# Circuit.net
KiCad netlist of a schematic drawn in EAGLE
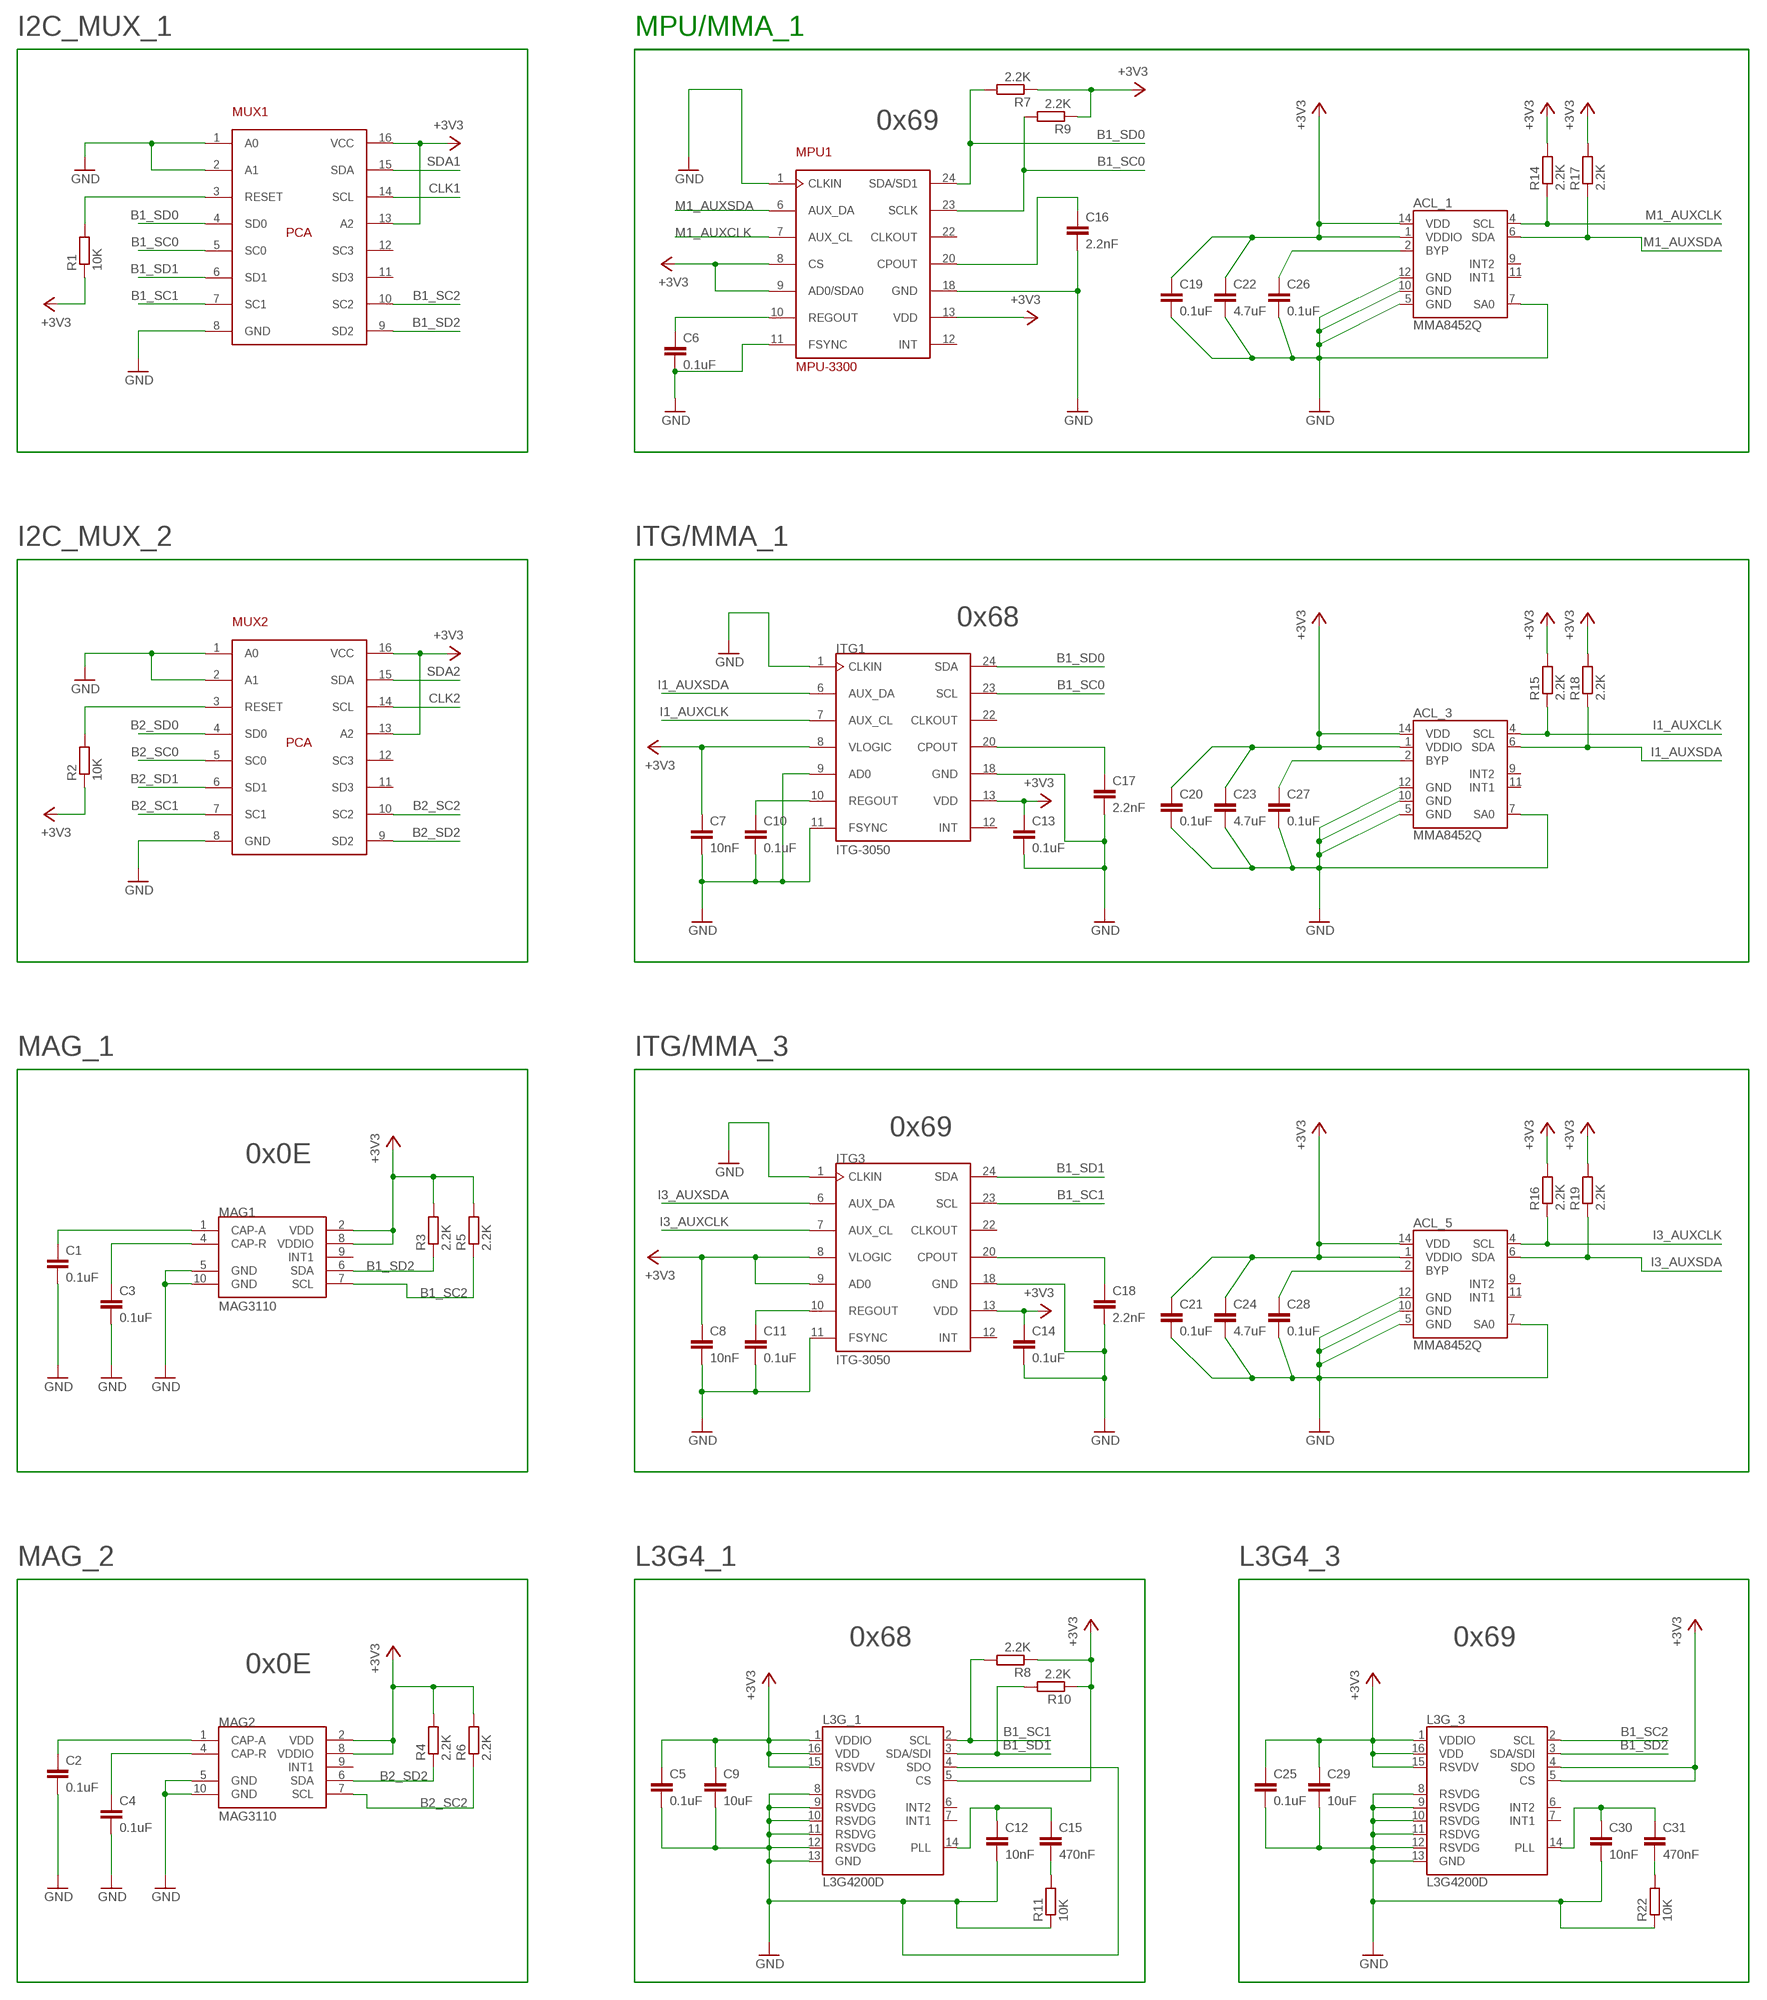
[diagram p0: schematic, sheet 1, part 1 of 2]
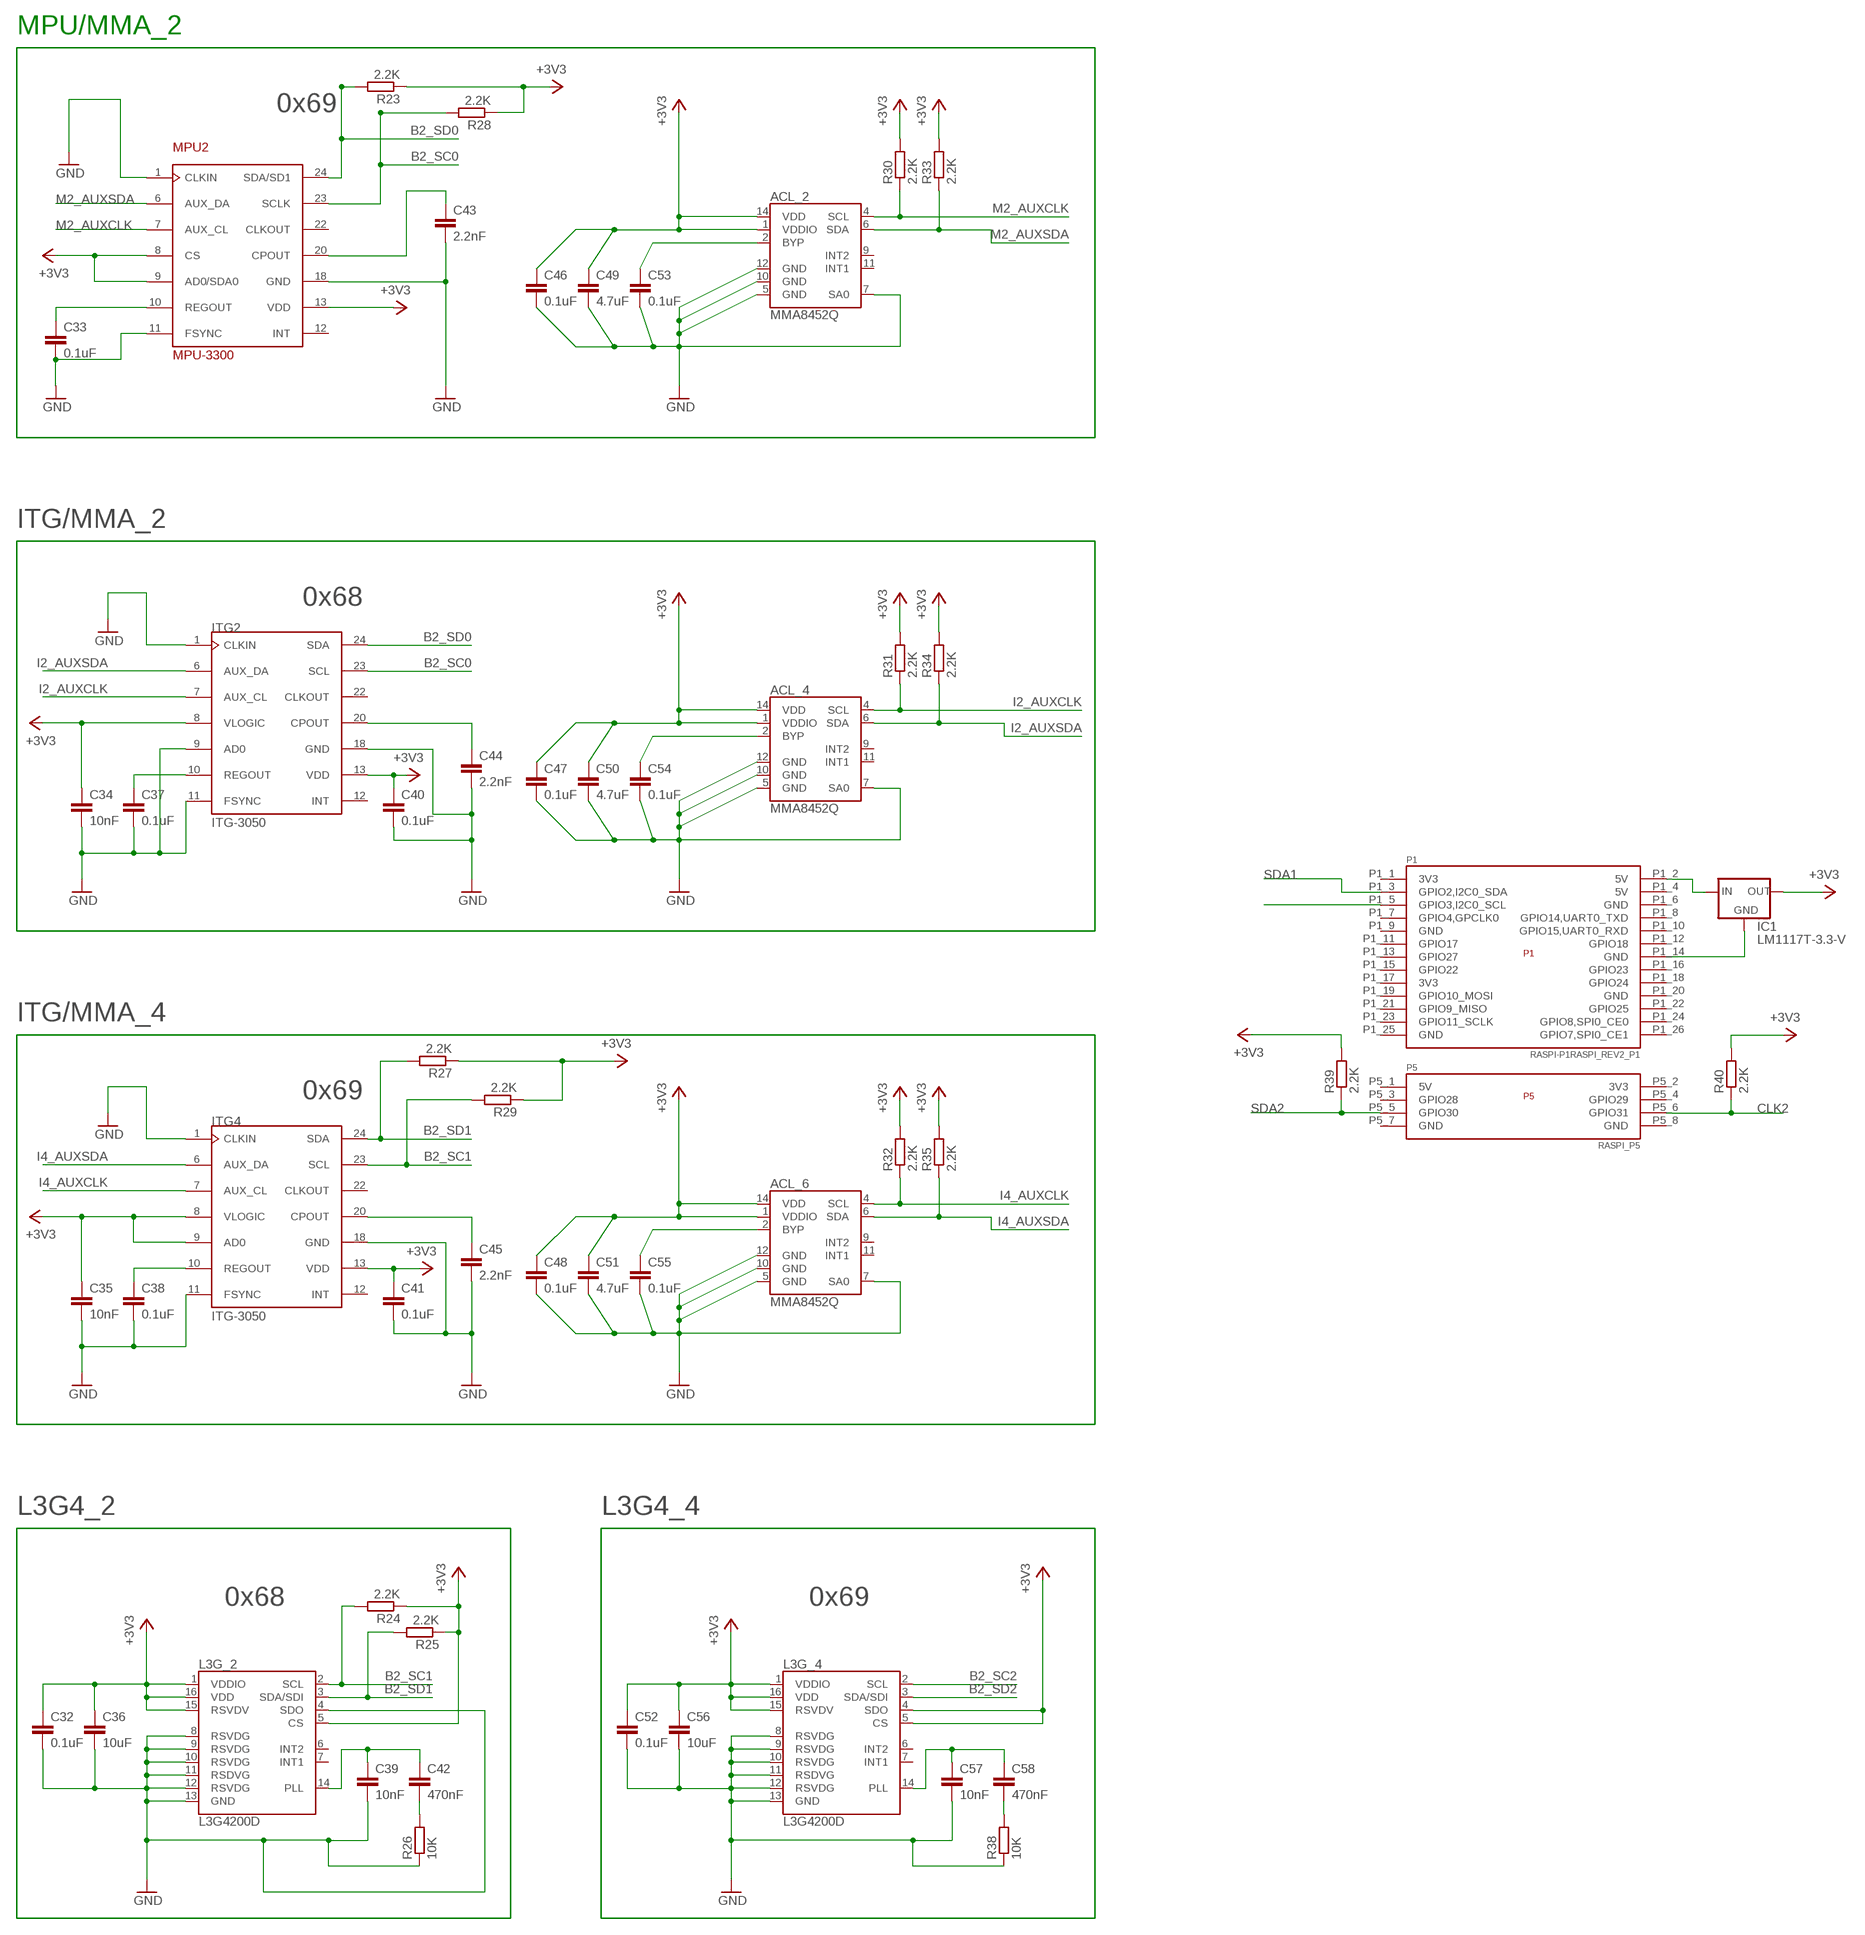
[diagram p1: schematic, sheet 1, part 2 of 2]

(export (version "E")
  (design (tool "Eeschema 10.0.6"))
  (components
    (comp (ref "ACL_1")
      (value "MMA8452Q")
      (footprint "eagle-import:QFN-16_0.5MM")
      (libsource (lib "eagle-import") (part "MMA8452Q"))
    )
    (comp (ref "ACL_2")
      (value "MMA8452Q")
      (footprint "eagle-import:QFN-16_0.5MM")
      (libsource (lib "eagle-import") (part "MMA8452Q"))
    )
    (comp (ref "ACL_3")
      (value "MMA8452Q")
      (footprint "eagle-import:QFN-16_0.5MM")
      (libsource (lib "eagle-import") (part "MMA8452Q"))
    )
    (comp (ref "ACL_4")
      (value "MMA8452Q")
      (footprint "eagle-import:QFN-16_0.5MM")
      (libsource (lib "eagle-import") (part "MMA8452Q"))
    )
    (comp (ref "ACL_5")
      (value "MMA8452Q")
      (footprint "eagle-import:QFN-16_0.5MM")
      (libsource (lib "eagle-import") (part "MMA8452Q"))
    )
    (comp (ref "ACL_6")
      (value "MMA8452Q")
      (footprint "eagle-import:QFN-16_0.5MM")
      (libsource (lib "eagle-import") (part "MMA8452Q"))
    )
    (comp (ref "C1")
      (value "0.1uF")
      (footprint "eagle-import:0603-CAP")
      (libsource (lib "eagle-import") (part "CAP0603-CAP"))
    )
    (comp (ref "C2")
      (value "0.1uF")
      (footprint "eagle-import:0603-CAP")
      (libsource (lib "eagle-import") (part "CAP0603-CAP"))
    )
    (comp (ref "C3")
      (value "0.1uF")
      (footprint "eagle-import:0603-CAP")
      (libsource (lib "eagle-import") (part "CAP0603-CAP"))
    )
    (comp (ref "C4")
      (value "0.1uF")
      (footprint "eagle-import:0603-CAP")
      (libsource (lib "eagle-import") (part "CAP0603-CAP"))
    )
    (comp (ref "C5")
      (value "0.1uF")
      (footprint "eagle-import:0603-CAP")
      (libsource (lib "eagle-import") (part "CAP0603-CAP"))
    )
    (comp (ref "C6")
      (value "0.1uF")
      (footprint "eagle-import:0603-CAP")
      (libsource (lib "eagle-import") (part "CAP0603-CAP"))
    )
    (comp (ref "C7")
      (value "10nF")
      (footprint "eagle-import:0603-CAP")
      (libsource (lib "eagle-import") (part "CAP0603-CAP"))
    )
    (comp (ref "C8")
      (value "10nF")
      (footprint "eagle-import:0603-CAP")
      (libsource (lib "eagle-import") (part "CAP0603-CAP"))
    )
    (comp (ref "C9")
      (value "10uF")
      (footprint "eagle-import:0603-CAP")
      (libsource (lib "eagle-import") (part "CAP0603-CAP"))
    )
    (comp (ref "C10")
      (value "0.1uF")
      (footprint "eagle-import:0603-CAP")
      (libsource (lib "eagle-import") (part "CAP0603-CAP"))
    )
    (comp (ref "C11")
      (value "0.1uF")
      (footprint "eagle-import:0603-CAP")
      (libsource (lib "eagle-import") (part "CAP0603-CAP"))
    )
    (comp (ref "C12")
      (value "10nF")
      (footprint "eagle-import:0603-CAP")
      (libsource (lib "eagle-import") (part "CAP0603-CAP"))
    )
    (comp (ref "C13")
      (value "0.1uF")
      (footprint "eagle-import:0603-CAP")
      (libsource (lib "eagle-import") (part "CAP0603-CAP"))
    )
    (comp (ref "C14")
      (value "0.1uF")
      (footprint "eagle-import:0603-CAP")
      (libsource (lib "eagle-import") (part "CAP0603-CAP"))
    )
    (comp (ref "C15")
      (value "470nF")
      (footprint "eagle-import:0603-CAP")
      (libsource (lib "eagle-import") (part "CAP0603-CAP"))
    )
    (comp (ref "C16")
      (value "2.2nF")
      (footprint "eagle-import:0603-CAP")
      (libsource (lib "eagle-import") (part "CAP0603-CAP"))
    )
    (comp (ref "C17")
      (value "2.2nF")
      (footprint "eagle-import:0603-CAP")
      (libsource (lib "eagle-import") (part "CAP0603-CAP"))
    )
    (comp (ref "C18")
      (value "2.2nF")
      (footprint "eagle-import:0603-CAP")
      (libsource (lib "eagle-import") (part "CAP0603-CAP"))
    )
    (comp (ref "C19")
      (value "0.1uF")
      (footprint "eagle-import:0603-CAP")
      (libsource (lib "eagle-import") (part "CAP0603-CAP"))
    )
    (comp (ref "C20")
      (value "0.1uF")
      (footprint "eagle-import:0603-CAP")
      (libsource (lib "eagle-import") (part "CAP0603-CAP"))
    )
    (comp (ref "C21")
      (value "0.1uF")
      (footprint "eagle-import:0603-CAP")
      (libsource (lib "eagle-import") (part "CAP0603-CAP"))
    )
    (comp (ref "C22")
      (value "4.7uF")
      (footprint "eagle-import:0603-CAP")
      (libsource (lib "eagle-import") (part "CAP0603-CAP"))
    )
    (comp (ref "C23")
      (value "4.7uF")
      (footprint "eagle-import:0603-CAP")
      (libsource (lib "eagle-import") (part "CAP0603-CAP"))
    )
    (comp (ref "C24")
      (value "4.7uF")
      (footprint "eagle-import:0603-CAP")
      (libsource (lib "eagle-import") (part "CAP0603-CAP"))
    )
    (comp (ref "C25")
      (value "0.1uF")
      (footprint "eagle-import:0603-CAP")
      (libsource (lib "eagle-import") (part "CAP0603-CAP"))
    )
    (comp (ref "C26")
      (value "0.1uF")
      (footprint "eagle-import:0603-CAP")
      (libsource (lib "eagle-import") (part "CAP0603-CAP"))
    )
    (comp (ref "C27")
      (value "0.1uF")
      (footprint "eagle-import:0603-CAP")
      (libsource (lib "eagle-import") (part "CAP0603-CAP"))
    )
    (comp (ref "C28")
      (value "0.1uF")
      (footprint "eagle-import:0603-CAP")
      (libsource (lib "eagle-import") (part "CAP0603-CAP"))
    )
    (comp (ref "C29")
      (value "10uF")
      (footprint "eagle-import:0603-CAP")
      (libsource (lib "eagle-import") (part "CAP0603-CAP"))
    )
    (comp (ref "C30")
      (value "10nF")
      (footprint "eagle-import:0603-CAP")
      (libsource (lib "eagle-import") (part "CAP0603-CAP"))
    )
    (comp (ref "C31")
      (value "470nF")
      (footprint "eagle-import:0603-CAP")
      (libsource (lib "eagle-import") (part "CAP0603-CAP"))
    )
    (comp (ref "C32")
      (value "0.1uF")
      (footprint "eagle-import:0603-CAP")
      (libsource (lib "eagle-import") (part "CAP0603-CAP"))
    )
    (comp (ref "C33")
      (value "0.1uF")
      (footprint "eagle-import:0603-CAP")
      (libsource (lib "eagle-import") (part "CAP0603-CAP"))
    )
    (comp (ref "C34")
      (value "10nF")
      (footprint "eagle-import:0603-CAP")
      (libsource (lib "eagle-import") (part "CAP0603-CAP"))
    )
    (comp (ref "C35")
      (value "10nF")
      (footprint "eagle-import:0603-CAP")
      (libsource (lib "eagle-import") (part "CAP0603-CAP"))
    )
    (comp (ref "C36")
      (value "10uF")
      (footprint "eagle-import:0603-CAP")
      (libsource (lib "eagle-import") (part "CAP0603-CAP"))
    )
    (comp (ref "C37")
      (value "0.1uF")
      (footprint "eagle-import:0603-CAP")
      (libsource (lib "eagle-import") (part "CAP0603-CAP"))
    )
    (comp (ref "C38")
      (value "0.1uF")
      (footprint "eagle-import:0603-CAP")
      (libsource (lib "eagle-import") (part "CAP0603-CAP"))
    )
    (comp (ref "C39")
      (value "10nF")
      (footprint "eagle-import:0603-CAP")
      (libsource (lib "eagle-import") (part "CAP0603-CAP"))
    )
    (comp (ref "C40")
      (value "0.1uF")
      (footprint "eagle-import:0603-CAP")
      (libsource (lib "eagle-import") (part "CAP0603-CAP"))
    )
    (comp (ref "C41")
      (value "0.1uF")
      (footprint "eagle-import:0603-CAP")
      (libsource (lib "eagle-import") (part "CAP0603-CAP"))
    )
    (comp (ref "C42")
      (value "470nF")
      (footprint "eagle-import:0603-CAP")
      (libsource (lib "eagle-import") (part "CAP0603-CAP"))
    )
    (comp (ref "C43")
      (value "2.2nF")
      (footprint "eagle-import:0603-CAP")
      (libsource (lib "eagle-import") (part "CAP0603-CAP"))
    )
    (comp (ref "C44")
      (value "2.2nF")
      (footprint "eagle-import:0603-CAP")
      (libsource (lib "eagle-import") (part "CAP0603-CAP"))
    )
    (comp (ref "C45")
      (value "2.2nF")
      (footprint "eagle-import:0603-CAP")
      (libsource (lib "eagle-import") (part "CAP0603-CAP"))
    )
    (comp (ref "C46")
      (value "0.1uF")
      (footprint "eagle-import:0603-CAP")
      (libsource (lib "eagle-import") (part "CAP0603-CAP"))
    )
    (comp (ref "C47")
      (value "0.1uF")
      (footprint "eagle-import:0603-CAP")
      (libsource (lib "eagle-import") (part "CAP0603-CAP"))
    )
    (comp (ref "C48")
      (value "0.1uF")
      (footprint "eagle-import:0603-CAP")
      (libsource (lib "eagle-import") (part "CAP0603-CAP"))
    )
    (comp (ref "C49")
      (value "4.7uF")
      (footprint "eagle-import:0603-CAP")
      (libsource (lib "eagle-import") (part "CAP0603-CAP"))
    )
    (comp (ref "C50")
      (value "4.7uF")
      (footprint "eagle-import:0603-CAP")
      (libsource (lib "eagle-import") (part "CAP0603-CAP"))
    )
    (comp (ref "C51")
      (value "4.7uF")
      (footprint "eagle-import:0603-CAP")
      (libsource (lib "eagle-import") (part "CAP0603-CAP"))
    )
    (comp (ref "C52")
      (value "0.1uF")
      (footprint "eagle-import:0603-CAP")
      (libsource (lib "eagle-import") (part "CAP0603-CAP"))
    )
    (comp (ref "C53")
      (value "0.1uF")
      (footprint "eagle-import:0603-CAP")
      (libsource (lib "eagle-import") (part "CAP0603-CAP"))
    )
    (comp (ref "C54")
      (value "0.1uF")
      (footprint "eagle-import:0603-CAP")
      (libsource (lib "eagle-import") (part "CAP0603-CAP"))
    )
    (comp (ref "C55")
      (value "0.1uF")
      (footprint "eagle-import:0603-CAP")
      (libsource (lib "eagle-import") (part "CAP0603-CAP"))
    )
    (comp (ref "C56")
      (value "10uF")
      (footprint "eagle-import:0603-CAP")
      (libsource (lib "eagle-import") (part "CAP0603-CAP"))
    )
    (comp (ref "C57")
      (value "10nF")
      (footprint "eagle-import:0603-CAP")
      (libsource (lib "eagle-import") (part "CAP0603-CAP"))
    )
    (comp (ref "C58")
      (value "470nF")
      (footprint "eagle-import:0603-CAP")
      (libsource (lib "eagle-import") (part "CAP0603-CAP"))
    )
    (comp (ref "IC1")
      (value "LM1117T-3.3-V")
      (footprint "eagle-import:TO220V")
      (libsource (lib "eagle-import") (part "LM1117T--V3.3"))
    )
    (comp (ref "ITG1")
      (value "ITG-3050")
      (footprint "eagle-import:QFN-24-4MM2")
      (libsource (lib "eagle-import") (part "ITG-3050"))
    )
    (comp (ref "ITG2")
      (value "ITG-3050")
      (footprint "eagle-import:QFN-24-4MM2")
      (libsource (lib "eagle-import") (part "ITG-3050"))
    )
    (comp (ref "ITG3")
      (value "ITG-3050")
      (footprint "eagle-import:QFN-24-4MM2")
      (libsource (lib "eagle-import") (part "ITG-3050"))
    )
    (comp (ref "ITG4")
      (value "ITG-3050")
      (footprint "eagle-import:QFN-24-4MM2")
      (libsource (lib "eagle-import") (part "ITG-3050"))
    )
    (comp (ref "L3G_1")
      (value "L3G4200D")
      (footprint "eagle-import:LGA16-4X4")
      (libsource (lib "eagle-import") (part "L3G4200D"))
    )
    (comp (ref "L3G_2")
      (value "L3G4200D")
      (footprint "eagle-import:LGA16-4X4")
      (libsource (lib "eagle-import") (part "L3G4200D"))
    )
    (comp (ref "L3G_3")
      (value "L3G4200D")
      (footprint "eagle-import:LGA16-4X4")
      (libsource (lib "eagle-import") (part "L3G4200D"))
    )
    (comp (ref "L3G_4")
      (value "L3G4200D")
      (footprint "eagle-import:LGA16-4X4")
      (libsource (lib "eagle-import") (part "L3G4200D"))
    )
    (comp (ref "MAG1")
      (value "MAG3110")
      (footprint "eagle-import:DFN-10")
      (libsource (lib "eagle-import") (part "MAG3110"))
    )
    (comp (ref "MAG2")
      (value "MAG3110")
      (footprint "eagle-import:DFN-10")
      (libsource (lib "eagle-import") (part "MAG3110"))
    )
    (comp (ref "MPU1")
      (value "MPU-3300")
      (footprint "eagle-import:QFN-24-4MM2")
      (libsource (lib "eagle-import") (part "MPU-3300"))
    )
    (comp (ref "MPU2")
      (value "MPU-3300")
      (footprint "eagle-import:QFN-24-4MM2")
      (libsource (lib "eagle-import") (part "MPU-3300"))
    )
    (comp (ref "MUX1")
      (value "PCA9546A")
      (footprint "eagle-import:TSSOP16")
      (libsource (lib "eagle-import") (part "PCA9546A"))
    )
    (comp (ref "MUX2")
      (value "PCA9546A")
      (footprint "eagle-import:TSSOP16")
      (libsource (lib "eagle-import") (part "PCA9546A"))
    )
    (comp (ref "P1")
      (value "RASPI-P1RASPI_REV2_P1")
      (footprint "eagle-import:RASPBERRY-PI_REV2")
      (libsource (lib "eagle-import") (part "RASPI-P1RASPI_REV2_P1"))
    )
    (comp (ref "P5")
      (value "RASPI_P5")
      (footprint "eagle-import:RASPI_P5")
      (libsource (lib "eagle-import") (part "RASPI_P5"))
    )
    (comp (ref "R1")
      (value "10K")
      (footprint "eagle-import:R0603")
      (libsource (lib "eagle-import") (part "R-EU_R0603"))
    )
    (comp (ref "R2")
      (value "10K")
      (footprint "eagle-import:R0603")
      (libsource (lib "eagle-import") (part "R-EU_R0603"))
    )
    (comp (ref "R3")
      (value "2.2K")
      (footprint "eagle-import:R0603")
      (libsource (lib "eagle-import") (part "R-EU_R0603"))
    )
    (comp (ref "R4")
      (value "2.2K")
      (footprint "eagle-import:R0603")
      (libsource (lib "eagle-import") (part "R-EU_R0603"))
    )
    (comp (ref "R5")
      (value "2.2K")
      (footprint "eagle-import:R0603")
      (libsource (lib "eagle-import") (part "R-EU_R0603"))
    )
    (comp (ref "R6")
      (value "2.2K")
      (footprint "eagle-import:R0603")
      (libsource (lib "eagle-import") (part "R-EU_R0603"))
    )
    (comp (ref "R7")
      (value "2.2K")
      (footprint "eagle-import:R0603")
      (libsource (lib "eagle-import") (part "R-EU_R0603"))
    )
    (comp (ref "R8")
      (value "2.2K")
      (footprint "eagle-import:R0603")
      (libsource (lib "eagle-import") (part "R-EU_R0603"))
    )
    (comp (ref "R9")
      (value "2.2K")
      (footprint "eagle-import:R0603")
      (libsource (lib "eagle-import") (part "R-EU_R0603"))
    )
    (comp (ref "R10")
      (value "2.2K")
      (footprint "eagle-import:R0603")
      (libsource (lib "eagle-import") (part "R-EU_R0603"))
    )
    (comp (ref "R11")
      (value "10K")
      (footprint "eagle-import:R0603")
      (libsource (lib "eagle-import") (part "R-EU_R0603"))
    )
    (comp (ref "R14")
      (value "2.2K")
      (footprint "eagle-import:R0603")
      (libsource (lib "eagle-import") (part "R-EU_R0603"))
    )
    (comp (ref "R15")
      (value "2.2K")
      (footprint "eagle-import:R0603")
      (libsource (lib "eagle-import") (part "R-EU_R0603"))
    )
    (comp (ref "R16")
      (value "2.2K")
      (footprint "eagle-import:R0603")
      (libsource (lib "eagle-import") (part "R-EU_R0603"))
    )
    (comp (ref "R17")
      (value "2.2K")
      (footprint "eagle-import:R0603")
      (libsource (lib "eagle-import") (part "R-EU_R0603"))
    )
    (comp (ref "R18")
      (value "2.2K")
      (footprint "eagle-import:R0603")
      (libsource (lib "eagle-import") (part "R-EU_R0603"))
    )
    (comp (ref "R19")
      (value "2.2K")
      (footprint "eagle-import:R0603")
      (libsource (lib "eagle-import") (part "R-EU_R0603"))
    )
    (comp (ref "R22")
      (value "10K")
      (footprint "eagle-import:R0603")
      (libsource (lib "eagle-import") (part "R-EU_R0603"))
    )
    (comp (ref "R23")
      (value "2.2K")
      (footprint "eagle-import:R0603")
      (libsource (lib "eagle-import") (part "R-EU_R0603"))
    )
    (comp (ref "R24")
      (value "2.2K")
      (footprint "eagle-import:R0603")
      (libsource (lib "eagle-import") (part "R-EU_R0603"))
    )
    (comp (ref "R25")
      (value "2.2K")
      (footprint "eagle-import:R0603")
      (libsource (lib "eagle-import") (part "R-EU_R0603"))
    )
    (comp (ref "R26")
      (value "10K")
      (footprint "eagle-import:R0603")
      (libsource (lib "eagle-import") (part "R-EU_R0603"))
    )
    (comp (ref "R27")
      (value "2.2K")
      (footprint "eagle-import:R0603")
      (libsource (lib "eagle-import") (part "R-EU_R0603"))
    )
    (comp (ref "R28")
      (value "2.2K")
      (footprint "eagle-import:R0603")
      (libsource (lib "eagle-import") (part "R-EU_R0603"))
    )
    (comp (ref "R29")
      (value "2.2K")
      (footprint "eagle-import:R0603")
      (libsource (lib "eagle-import") (part "R-EU_R0603"))
    )
    (comp (ref "R30")
      (value "2.2K")
      (footprint "eagle-import:R0603")
      (libsource (lib "eagle-import") (part "R-EU_R0603"))
    )
    (comp (ref "R31")
      (value "2.2K")
      (footprint "eagle-import:R0603")
      (libsource (lib "eagle-import") (part "R-EU_R0603"))
    )
    (comp (ref "R32")
      (value "2.2K")
      (footprint "eagle-import:R0603")
      (libsource (lib "eagle-import") (part "R-EU_R0603"))
    )
    (comp (ref "R33")
      (value "2.2K")
      (footprint "eagle-import:R0603")
      (libsource (lib "eagle-import") (part "R-EU_R0603"))
    )
    (comp (ref "R34")
      (value "2.2K")
      (footprint "eagle-import:R0603")
      (libsource (lib "eagle-import") (part "R-EU_R0603"))
    )
    (comp (ref "R35")
      (value "2.2K")
      (footprint "eagle-import:R0603")
      (libsource (lib "eagle-import") (part "R-EU_R0603"))
    )
    (comp (ref "R38")
      (value "10K")
      (footprint "eagle-import:R0603")
      (libsource (lib "eagle-import") (part "R-EU_R0603"))
    )
    (comp (ref "R39")
      (value "2.2K")
      (footprint "eagle-import:R0603")
      (libsource (lib "eagle-import") (part "R-EU_R0603"))
    )
    (comp (ref "R40")
      (value "2.2K")
      (footprint "eagle-import:R0603")
      (libsource (lib "eagle-import") (part "R-EU_R0603"))
    )
  )
  (nets
    (net (code "1") (name "+3V3") (class "Default")
      (node (ref "ACL_1") (pin "1") (pinfunction "VDDIO_1") (pintype "bidirectional"))
      (node (ref "ACL_1") (pin "14") (pinfunction "VDD_14") (pintype "bidirectional"))
      (node (ref "ACL_2") (pin "1") (pinfunction "VDDIO_1") (pintype "bidirectional"))
      (node (ref "ACL_2") (pin "14") (pinfunction "VDD_14") (pintype "bidirectional"))
      (node (ref "ACL_3") (pin "1") (pinfunction "VDDIO_1") (pintype "bidirectional"))
      (node (ref "ACL_3") (pin "14") (pinfunction "VDD_14") (pintype "bidirectional"))
      (node (ref "ACL_4") (pin "1") (pinfunction "VDDIO_1") (pintype "bidirectional"))
      (node (ref "ACL_4") (pin "14") (pinfunction "VDD_14") (pintype "bidirectional"))
      (node (ref "ACL_5") (pin "1") (pinfunction "VDDIO_1") (pintype "bidirectional"))
      (node (ref "ACL_5") (pin "14") (pinfunction "VDD_14") (pintype "bidirectional"))
      (node (ref "ACL_6") (pin "1") (pinfunction "VDDIO_1") (pintype "bidirectional"))
      (node (ref "ACL_6") (pin "14") (pinfunction "VDD_14") (pintype "bidirectional"))
      (node (ref "C13") (pin "1") (pinfunction "1_1") (pintype "passive"))
      (node (ref "C14") (pin "1") (pinfunction "1_1") (pintype "passive"))
      (node (ref "C19") (pin "1") (pinfunction "1_1") (pintype "passive"))
      (node (ref "C20") (pin "1") (pinfunction "1_1") (pintype "passive"))
      (node (ref "C21") (pin "1") (pinfunction "1_1") (pintype "passive"))
      (node (ref "C22") (pin "1") (pinfunction "1_1") (pintype "passive"))
      (node (ref "C23") (pin "1") (pinfunction "1_1") (pintype "passive"))
      (node (ref "C24") (pin "1") (pinfunction "1_1") (pintype "passive"))
      (node (ref "C25") (pin "1") (pinfunction "1_1") (pintype "passive"))
      (node (ref "C29") (pin "1") (pinfunction "1_1") (pintype "passive"))
      (node (ref "C32") (pin "1") (pinfunction "1_1") (pintype "passive"))
      (node (ref "C34") (pin "1") (pinfunction "1_1") (pintype "passive"))
      (node (ref "C35") (pin "1") (pinfunction "1_1") (pintype "passive"))
      (node (ref "C36") (pin "1") (pinfunction "1_1") (pintype "passive"))
      (node (ref "C40") (pin "1") (pinfunction "1_1") (pintype "passive"))
      (node (ref "C41") (pin "1") (pinfunction "1_1") (pintype "passive"))
      (node (ref "C46") (pin "1") (pinfunction "1_1") (pintype "passive"))
      (node (ref "C47") (pin "1") (pinfunction "1_1") (pintype "passive"))
      (node (ref "C48") (pin "1") (pinfunction "1_1") (pintype "passive"))
      (node (ref "C49") (pin "1") (pinfunction "1_1") (pintype "passive"))
      (node (ref "C5") (pin "1") (pinfunction "1_1") (pintype "passive"))
      (node (ref "C50") (pin "1") (pinfunction "1_1") (pintype "passive"))
      (node (ref "C51") (pin "1") (pinfunction "1_1") (pintype "passive"))
      (node (ref "C52") (pin "1") (pinfunction "1_1") (pintype "passive"))
      (node (ref "C56") (pin "1") (pinfunction "1_1") (pintype "passive"))
      (node (ref "C7") (pin "1") (pinfunction "1_1") (pintype "passive"))
      (node (ref "C8") (pin "1") (pinfunction "1_1") (pintype "passive"))
      (node (ref "C9") (pin "1") (pinfunction "1_1") (pintype "passive"))
      (node (ref "IC1") (pin "2") (pinfunction "OUT_2") (pintype "passive"))
      (node (ref "ITG1") (pin "13") (pinfunction "VDD_13") (pintype "bidirectional"))
      (node (ref "ITG1") (pin "8") (pinfunction "VLOGIC_8") (pintype "bidirectional"))
      (node (ref "ITG2") (pin "13") (pinfunction "VDD_13") (pintype "bidirectional"))
      (node (ref "ITG2") (pin "8") (pinfunction "VLOGIC_8") (pintype "bidirectional"))
      (node (ref "ITG3") (pin "13") (pinfunction "VDD_13") (pintype "bidirectional"))
      (node (ref "ITG3") (pin "8") (pinfunction "VLOGIC_8") (pintype "bidirectional"))
      (node (ref "ITG3") (pin "9") (pinfunction "AD0_9") (pintype "bidirectional"))
      (node (ref "ITG4") (pin "13") (pinfunction "VDD_13") (pintype "bidirectional"))
      (node (ref "ITG4") (pin "8") (pinfunction "VLOGIC_8") (pintype "bidirectional"))
      (node (ref "ITG4") (pin "9") (pinfunction "AD0_9") (pintype "bidirectional"))
      (node (ref "L3G_1") (pin "1") (pinfunction "VDDIO_1") (pintype "bidirectional"))
      (node (ref "L3G_1") (pin "15") (pinfunction "RSVDV_15") (pintype "bidirectional"))
      (node (ref "L3G_1") (pin "16") (pinfunction "VDD_16") (pintype "bidirectional"))
      (node (ref "L3G_1") (pin "5") (pinfunction "CS_5") (pintype "bidirectional"))
      (node (ref "L3G_2") (pin "1") (pinfunction "VDDIO_1") (pintype "bidirectional"))
      (node (ref "L3G_2") (pin "15") (pinfunction "RSVDV_15") (pintype "bidirectional"))
      (node (ref "L3G_2") (pin "16") (pinfunction "VDD_16") (pintype "bidirectional"))
      (node (ref "L3G_2") (pin "5") (pinfunction "CS_5") (pintype "bidirectional"))
      (node (ref "L3G_3") (pin "1") (pinfunction "VDDIO_1") (pintype "bidirectional"))
      (node (ref "L3G_3") (pin "15") (pinfunction "RSVDV_15") (pintype "bidirectional"))
      (node (ref "L3G_3") (pin "16") (pinfunction "VDD_16") (pintype "bidirectional"))
      (node (ref "L3G_3") (pin "4") (pinfunction "SDO_4") (pintype "bidirectional"))
      (node (ref "L3G_3") (pin "5") (pinfunction "CS_5") (pintype "bidirectional"))
      (node (ref "L3G_4") (pin "1") (pinfunction "VDDIO_1") (pintype "bidirectional"))
      (node (ref "L3G_4") (pin "15") (pinfunction "RSVDV_15") (pintype "bidirectional"))
      (node (ref "L3G_4") (pin "16") (pinfunction "VDD_16") (pintype "bidirectional"))
      (node (ref "L3G_4") (pin "4") (pinfunction "SDO_4") (pintype "bidirectional"))
      (node (ref "L3G_4") (pin "5") (pinfunction "CS_5") (pintype "bidirectional"))
      (node (ref "MAG1") (pin "2") (pinfunction "VDD_2") (pintype "bidirectional"))
      (node (ref "MAG1") (pin "8") (pinfunction "VDDIO_8") (pintype "bidirectional"))
      (node (ref "MAG2") (pin "2") (pinfunction "VDD_2") (pintype "bidirectional"))
      (node (ref "MAG2") (pin "8") (pinfunction "VDDIO_8") (pintype "bidirectional"))
      (node (ref "MPU1") (pin "13") (pinfunction "VDD_13") (pintype "bidirectional"))
      (node (ref "MPU1") (pin "8") (pinfunction "CS_8") (pintype "bidirectional"))
      (node (ref "MPU1") (pin "9") (pinfunction "AD0/SDA0_9") (pintype "bidirectional"))
      (node (ref "MPU2") (pin "13") (pinfunction "VDD_13") (pintype "bidirectional"))
      (node (ref "MPU2") (pin "8") (pinfunction "CS_8") (pintype "bidirectional"))
      (node (ref "MPU2") (pin "9") (pinfunction "AD0/SDA0_9") (pintype "bidirectional"))
      (node (ref "MUX1") (pin "13") (pinfunction "A2_13") (pintype "bidirectional"))
      (node (ref "MUX1") (pin "16") (pinfunction "VCC_16") (pintype "bidirectional"))
      (node (ref "MUX2") (pin "13") (pinfunction "A2_13") (pintype "bidirectional"))
      (node (ref "MUX2") (pin "16") (pinfunction "VCC_16") (pintype "bidirectional"))
      (node (ref "R1") (pin "1") (pinfunction "1_1") (pintype "passive"))
      (node (ref "R10") (pin "1") (pinfunction "1_1") (pintype "passive"))
      (node (ref "R14") (pin "2") (pinfunction "2_2") (pintype "passive"))
      (node (ref "R15") (pin "2") (pinfunction "2_2") (pintype "passive"))
      (node (ref "R16") (pin "2") (pinfunction "2_2") (pintype "passive"))
      (node (ref "R17") (pin "2") (pinfunction "2_2") (pintype "passive"))
      (node (ref "R18") (pin "2") (pinfunction "2_2") (pintype "passive"))
      (node (ref "R19") (pin "2") (pinfunction "2_2") (pintype "passive"))
      (node (ref "R2") (pin "1") (pinfunction "1_1") (pintype "passive"))
      (node (ref "R23") (pin "1") (pinfunction "1_1") (pintype "passive"))
      (node (ref "R24") (pin "1") (pinfunction "1_1") (pintype "passive"))
      (node (ref "R25") (pin "1") (pinfunction "1_1") (pintype "passive"))
      (node (ref "R27") (pin "1") (pinfunction "1_1") (pintype "passive"))
      (node (ref "R28") (pin "1") (pinfunction "1_1") (pintype "passive"))
      (node (ref "R29") (pin "1") (pinfunction "1_1") (pintype "passive"))
      (node (ref "R3") (pin "2") (pinfunction "2_2") (pintype "passive"))
      (node (ref "R30") (pin "2") (pinfunction "2_2") (pintype "passive"))
      (node (ref "R31") (pin "2") (pinfunction "2_2") (pintype "passive"))
      (node (ref "R32") (pin "2") (pinfunction "2_2") (pintype "passive"))
      (node (ref "R33") (pin "2") (pinfunction "2_2") (pintype "passive"))
      (node (ref "R34") (pin "2") (pinfunction "2_2") (pintype "passive"))
      (node (ref "R35") (pin "2") (pinfunction "2_2") (pintype "passive"))
      (node (ref "R39") (pin "2") (pinfunction "2_2") (pintype "passive"))
      (node (ref "R4") (pin "2") (pinfunction "2_2") (pintype "passive"))
      (node (ref "R40") (pin "2") (pinfunction "2_2") (pintype "passive"))
      (node (ref "R5") (pin "2") (pinfunction "2_2") (pintype "passive"))
      (node (ref "R6") (pin "2") (pinfunction "2_2") (pintype "passive"))
      (node (ref "R7") (pin "1") (pinfunction "1_1") (pintype "passive"))
      (node (ref "R8") (pin "1") (pinfunction "1_1") (pintype "passive"))
      (node (ref "R9") (pin "1") (pinfunction "1_1") (pintype "passive"))
    )
    (net (code "2") (name "/B1_SC0") (class "Default")
      (node (ref "ITG1") (pin "23") (pinfunction "SCL_23") (pintype "bidirectional"))
      (node (ref "MPU1") (pin "23") (pinfunction "SCLK_23") (pintype "bidirectional"))
      (node (ref "MUX1") (pin "5") (pinfunction "SC0_5") (pintype "bidirectional"))
      (node (ref "R9") (pin "2") (pinfunction "2_2") (pintype "passive"))
    )
    (net (code "3") (name "/B1_SC1") (class "Default")
      (node (ref "ITG3") (pin "23") (pinfunction "SCL_23") (pintype "bidirectional"))
      (node (ref "L3G_1") (pin "2") (pinfunction "SCL_2") (pintype "bidirectional"))
      (node (ref "MUX1") (pin "7") (pinfunction "SC1_7") (pintype "bidirectional"))
      (node (ref "R8") (pin "2") (pinfunction "2_2") (pintype "passive"))
    )
    (net (code "4") (name "/B1_SC2") (class "Default")
      (node (ref "L3G_3") (pin "2") (pinfunction "SCL_2") (pintype "bidirectional"))
      (node (ref "MAG1") (pin "7") (pinfunction "SCL_7") (pintype "bidirectional"))
      (node (ref "MUX1") (pin "10") (pinfunction "SC2_10") (pintype "bidirectional"))
      (node (ref "R5") (pin "1") (pinfunction "1_1") (pintype "passive"))
    )
    (net (code "5") (name "/B1_SD0") (class "Default")
      (node (ref "ITG1") (pin "24") (pinfunction "SDA_24") (pintype "bidirectional"))
      (node (ref "MPU1") (pin "24") (pinfunction "SDA/SD1_24") (pintype "bidirectional"))
      (node (ref "MUX1") (pin "4") (pinfunction "SD0_4") (pintype "bidirectional"))
      (node (ref "R7") (pin "2") (pinfunction "2_2") (pintype "passive"))
    )
    (net (code "6") (name "/B1_SD1") (class "Default")
      (node (ref "ITG3") (pin "24") (pinfunction "SDA_24") (pintype "bidirectional"))
      (node (ref "L3G_1") (pin "3") (pinfunction "SDA/SDI_3") (pintype "bidirectional"))
      (node (ref "MUX1") (pin "6") (pinfunction "SD1_6") (pintype "bidirectional"))
      (node (ref "R10") (pin "2") (pinfunction "2_2") (pintype "passive"))
    )
    (net (code "7") (name "/B1_SD2") (class "Default")
      (node (ref "L3G_3") (pin "3") (pinfunction "SDA/SDI_3") (pintype "bidirectional"))
      (node (ref "MAG1") (pin "6") (pinfunction "SDA_6") (pintype "bidirectional"))
      (node (ref "MUX1") (pin "9") (pinfunction "SD2_9") (pintype "bidirectional"))
      (node (ref "R3") (pin "1") (pinfunction "1_1") (pintype "passive"))
    )
    (net (code "8") (name "/B2_SC0") (class "Default")
      (node (ref "ITG2") (pin "23") (pinfunction "SCL_23") (pintype "bidirectional"))
      (node (ref "MPU2") (pin "23") (pinfunction "SCLK_23") (pintype "bidirectional"))
      (node (ref "MUX2") (pin "5") (pinfunction "SC0_5") (pintype "bidirectional"))
      (node (ref "R28") (pin "2") (pinfunction "2_2") (pintype "passive"))
    )
    (net (code "9") (name "/B2_SC1") (class "Default")
      (node (ref "ITG4") (pin "23") (pinfunction "SCL_23") (pintype "bidirectional"))
      (node (ref "L3G_2") (pin "2") (pinfunction "SCL_2") (pintype "bidirectional"))
      (node (ref "MUX2") (pin "7") (pinfunction "SC1_7") (pintype "bidirectional"))
      (node (ref "R24") (pin "2") (pinfunction "2_2") (pintype "passive"))
      (node (ref "R29") (pin "2") (pinfunction "2_2") (pintype "passive"))
    )
    (net (code "10") (name "/B2_SC2") (class "Default")
      (node (ref "L3G_4") (pin "2") (pinfunction "SCL_2") (pintype "bidirectional"))
      (node (ref "MAG2") (pin "7") (pinfunction "SCL_7") (pintype "bidirectional"))
      (node (ref "MUX2") (pin "10") (pinfunction "SC2_10") (pintype "bidirectional"))
      (node (ref "R6") (pin "1") (pinfunction "1_1") (pintype "passive"))
    )
    (net (code "11") (name "/B2_SD0") (class "Default")
      (node (ref "ITG2") (pin "24") (pinfunction "SDA_24") (pintype "bidirectional"))
      (node (ref "MPU2") (pin "24") (pinfunction "SDA/SD1_24") (pintype "bidirectional"))
      (node (ref "MUX2") (pin "4") (pinfunction "SD0_4") (pintype "bidirectional"))
      (node (ref "R23") (pin "2") (pinfunction "2_2") (pintype "passive"))
    )
    (net (code "12") (name "/B2_SD1") (class "Default")
      (node (ref "ITG4") (pin "24") (pinfunction "SDA_24") (pintype "bidirectional"))
      (node (ref "L3G_2") (pin "3") (pinfunction "SDA/SDI_3") (pintype "bidirectional"))
      (node (ref "MUX2") (pin "6") (pinfunction "SD1_6") (pintype "bidirectional"))
      (node (ref "R25") (pin "2") (pinfunction "2_2") (pintype "passive"))
      (node (ref "R27") (pin "2") (pinfunction "2_2") (pintype "passive"))
    )
    (net (code "13") (name "/B2_SD2") (class "Default")
      (node (ref "L3G_4") (pin "3") (pinfunction "SDA/SDI_3") (pintype "bidirectional"))
      (node (ref "MAG2") (pin "6") (pinfunction "SDA_6") (pintype "bidirectional"))
      (node (ref "MUX2") (pin "9") (pinfunction "SD2_9") (pintype "bidirectional"))
      (node (ref "R4") (pin "1") (pinfunction "1_1") (pintype "passive"))
    )
    (net (code "14") (name "/CLK1") (class "Default")
      (node (ref "MUX1") (pin "14") (pinfunction "SCL_14") (pintype "bidirectional"))
      (node (ref "P1") (pin "P1_5") (pinfunction "GPIO3,I2C0_SCL_P1_5") (pintype "bidirectional"))
    )
    (net (code "15") (name "/CLK2") (class "Default")
      (node (ref "MUX2") (pin "14") (pinfunction "SCL_14") (pintype "bidirectional"))
      (node (ref "P5") (pin "P5_6") (pinfunction "GPIO31_P5_6") (pintype "bidirectional"))
      (node (ref "R40") (pin "1") (pinfunction "1_1") (pintype "passive"))
    )
    (net (code "16") (name "/I1_AUXCLK") (class "Default")
      (node (ref "ACL_3") (pin "4") (pinfunction "SCL_4") (pintype "bidirectional"))
      (node (ref "ITG1") (pin "7") (pinfunction "AUX_CL_7") (pintype "bidirectional"))
      (node (ref "R15") (pin "1") (pinfunction "1_1") (pintype "passive"))
    )
    (net (code "17") (name "/I1_AUXSDA") (class "Default")
      (node (ref "ACL_3") (pin "6") (pinfunction "SDA_6") (pintype "bidirectional"))
      (node (ref "ITG1") (pin "6") (pinfunction "AUX_DA_6") (pintype "bidirectional"))
      (node (ref "R18") (pin "1") (pinfunction "1_1") (pintype "passive"))
    )
    (net (code "20") (name "/I2_AUXCLK") (class "Default")
      (node (ref "ACL_4") (pin "4") (pinfunction "SCL_4") (pintype "bidirectional"))
      (node (ref "ITG2") (pin "7") (pinfunction "AUX_CL_7") (pintype "bidirectional"))
      (node (ref "R31") (pin "1") (pinfunction "1_1") (pintype "passive"))
    )
    (net (code "21") (name "/I2_AUXSDA") (class "Default")
      (node (ref "ACL_4") (pin "6") (pinfunction "SDA_6") (pintype "bidirectional"))
      (node (ref "ITG2") (pin "6") (pinfunction "AUX_DA_6") (pintype "bidirectional"))
      (node (ref "R34") (pin "1") (pinfunction "1_1") (pintype "passive"))
    )
    (net (code "22") (name "/I3_AUXCLK") (class "Default")
      (node (ref "ACL_5") (pin "4") (pinfunction "SCL_4") (pintype "bidirectional"))
      (node (ref "ITG3") (pin "7") (pinfunction "AUX_CL_7") (pintype "bidirectional"))
      (node (ref "R16") (pin "1") (pinfunction "1_1") (pintype "passive"))
    )
    (net (code "23") (name "/I3_AUXSDA") (class "Default")
      (node (ref "ACL_5") (pin "6") (pinfunction "SDA_6") (pintype "bidirectional"))
      (node (ref "ITG3") (pin "6") (pinfunction "AUX_DA_6") (pintype "bidirectional"))
      (node (ref "R19") (pin "1") (pinfunction "1_1") (pintype "passive"))
    )
    (net (code "24") (name "/I4_AUXCLK") (class "Default")
      (node (ref "ACL_6") (pin "4") (pinfunction "SCL_4") (pintype "bidirectional"))
      (node (ref "ITG4") (pin "7") (pinfunction "AUX_CL_7") (pintype "bidirectional"))
      (node (ref "R32") (pin "1") (pinfunction "1_1") (pintype "passive"))
    )
    (net (code "25") (name "/I4_AUXSDA") (class "Default")
      (node (ref "ACL_6") (pin "6") (pinfunction "SDA_6") (pintype "bidirectional"))
      (node (ref "ITG4") (pin "6") (pinfunction "AUX_DA_6") (pintype "bidirectional"))
      (node (ref "R35") (pin "1") (pinfunction "1_1") (pintype "passive"))
    )
    (net (code "34") (name "/M1_AUXCLK") (class "Default")
      (node (ref "ACL_1") (pin "4") (pinfunction "SCL_4") (pintype "bidirectional"))
      (node (ref "MPU1") (pin "7") (pinfunction "AUX_CL_7") (pintype "bidirectional"))
      (node (ref "R14") (pin "1") (pinfunction "1_1") (pintype "passive"))
    )
    (net (code "35") (name "/M1_AUXSDA") (class "Default")
      (node (ref "ACL_1") (pin "6") (pinfunction "SDA_6") (pintype "bidirectional"))
      (node (ref "MPU1") (pin "6") (pinfunction "AUX_DA_6") (pintype "bidirectional"))
      (node (ref "R17") (pin "1") (pinfunction "1_1") (pintype "passive"))
    )
    (net (code "36") (name "/M2_AUXCLK") (class "Default")
      (node (ref "ACL_2") (pin "4") (pinfunction "SCL_4") (pintype "bidirectional"))
      (node (ref "MPU2") (pin "7") (pinfunction "AUX_CL_7") (pintype "bidirectional"))
      (node (ref "R30") (pin "1") (pinfunction "1_1") (pintype "passive"))
    )
    (net (code "37") (name "/M2_AUXSDA") (class "Default")
      (node (ref "ACL_2") (pin "6") (pinfunction "SDA_6") (pintype "bidirectional"))
      (node (ref "MPU2") (pin "6") (pinfunction "AUX_DA_6") (pintype "bidirectional"))
      (node (ref "R33") (pin "1") (pinfunction "1_1") (pintype "passive"))
    )
    (net (code "40") (name "/SDA1") (class "Default")
      (node (ref "MUX1") (pin "15") (pinfunction "SDA_15") (pintype "bidirectional"))
      (node (ref "P1") (pin "P1_3") (pinfunction "GPIO2,I2C0_SDA_P1_3") (pintype "bidirectional"))
    )
    (net (code "41") (name "/SDA2") (class "Default")
      (node (ref "MUX2") (pin "15") (pinfunction "SDA_15") (pintype "bidirectional"))
      (node (ref "P5") (pin "P5_5") (pinfunction "GPIO30_P5_5") (pintype "bidirectional"))
      (node (ref "R39") (pin "1") (pinfunction "1_1") (pintype "passive"))
    )
    (net (code "42") (name "GND") (class "Default")
      (node (ref "ACL_1") (pin "10") (pinfunction "GND_10") (pintype "bidirectional"))
      (node (ref "ACL_1") (pin "12") (pinfunction "GND_12") (pintype "bidirectional"))
      (node (ref "ACL_1") (pin "5") (pinfunction "GND_5") (pintype "bidirectional"))
      (node (ref "ACL_1") (pin "7") (pinfunction "SA0_7") (pintype "bidirectional"))
      (node (ref "ACL_2") (pin "10") (pinfunction "GND_10") (pintype "bidirectional"))
      (node (ref "ACL_2") (pin "12") (pinfunction "GND_12") (pintype "bidirectional"))
      (node (ref "ACL_2") (pin "5") (pinfunction "GND_5") (pintype "bidirectional"))
      (node (ref "ACL_2") (pin "7") (pinfunction "SA0_7") (pintype "bidirectional"))
      (node (ref "ACL_3") (pin "10") (pinfunction "GND_10") (pintype "bidirectional"))
      (node (ref "ACL_3") (pin "12") (pinfunction "GND_12") (pintype "bidirectional"))
      (node (ref "ACL_3") (pin "5") (pinfunction "GND_5") (pintype "bidirectional"))
      (node (ref "ACL_3") (pin "7") (pinfunction "SA0_7") (pintype "bidirectional"))
      (node (ref "ACL_4") (pin "10") (pinfunction "GND_10") (pintype "bidirectional"))
      (node (ref "ACL_4") (pin "12") (pinfunction "GND_12") (pintype "bidirectional"))
      (node (ref "ACL_4") (pin "5") (pinfunction "GND_5") (pintype "bidirectional"))
      (node (ref "ACL_4") (pin "7") (pinfunction "SA0_7") (pintype "bidirectional"))
      (node (ref "ACL_5") (pin "10") (pinfunction "GND_10") (pintype "bidirectional"))
      (node (ref "ACL_5") (pin "12") (pinfunction "GND_12") (pintype "bidirectional"))
      (node (ref "ACL_5") (pin "5") (pinfunction "GND_5") (pintype "bidirectional"))
      (node (ref "ACL_5") (pin "7") (pinfunction "SA0_7") (pintype "bidirectional"))
      (node (ref "ACL_6") (pin "10") (pinfunction "GND_10") (pintype "bidirectional"))
      (node (ref "ACL_6") (pin "12") (pinfunction "GND_12") (pintype "bidirectional"))
      (node (ref "ACL_6") (pin "5") (pinfunction "GND_5") (pintype "bidirectional"))
      (node (ref "ACL_6") (pin "7") (pinfunction "SA0_7") (pintype "bidirectional"))
      (node (ref "C1") (pin "2") (pinfunction "2_2") (pintype "passive"))
      (node (ref "C10") (pin "2") (pinfunction "2_2") (pintype "passive"))
      (node (ref "C11") (pin "2") (pinfunction "2_2") (pintype "passive"))
      (node (ref "C12") (pin "2") (pinfunction "2_2") (pintype "passive"))
      (node (ref "C13") (pin "2") (pinfunction "2_2") (pintype "passive"))
      (node (ref "C14") (pin "2") (pinfunction "2_2") (pintype "passive"))
      (node (ref "C16") (pin "2") (pinfunction "2_2") (pintype "passive"))
      (node (ref "C17") (pin "2") (pinfunction "2_2") (pintype "passive"))
      (node (ref "C18") (pin "2") (pinfunction "2_2") (pintype "passive"))
      (node (ref "C19") (pin "2") (pinfunction "2_2") (pintype "passive"))
      (node (ref "C2") (pin "2") (pinfunction "2_2") (pintype "passive"))
      (node (ref "C20") (pin "2") (pinfunction "2_2") (pintype "passive"))
      (node (ref "C21") (pin "2") (pinfunction "2_2") (pintype "passive"))
      (node (ref "C22") (pin "2") (pinfunction "2_2") (pintype "passive"))
      (node (ref "C23") (pin "2") (pinfunction "2_2") (pintype "passive"))
      (node (ref "C24") (pin "2") (pinfunction "2_2") (pintype "passive"))
      (node (ref "C25") (pin "2") (pinfunction "2_2") (pintype "passive"))
      (node (ref "C26") (pin "2") (pinfunction "2_2") (pintype "passive"))
      (node (ref "C27") (pin "2") (pinfunction "2_2") (pintype "passive"))
      (node (ref "C28") (pin "2") (pinfunction "2_2") (pintype "passive"))
      (node (ref "C29") (pin "2") (pinfunction "2_2") (pintype "passive"))
      (node (ref "C3") (pin "2") (pinfunction "2_2") (pintype "passive"))
      (node (ref "C30") (pin "2") (pinfunction "2_2") (pintype "passive"))
      (node (ref "C32") (pin "2") (pinfunction "2_2") (pintype "passive"))
      (node (ref "C33") (pin "2") (pinfunction "2_2") (pintype "passive"))
      (node (ref "C34") (pin "2") (pinfunction "2_2") (pintype "passive"))
      (node (ref "C35") (pin "2") (pinfunction "2_2") (pintype "passive"))
      (node (ref "C36") (pin "2") (pinfunction "2_2") (pintype "passive"))
      (node (ref "C37") (pin "2") (pinfunction "2_2") (pintype "passive"))
      (node (ref "C38") (pin "2") (pinfunction "2_2") (pintype "passive"))
      (node (ref "C39") (pin "2") (pinfunction "2_2") (pintype "passive"))
      (node (ref "C4") (pin "2") (pinfunction "2_2") (pintype "passive"))
      (node (ref "C40") (pin "2") (pinfunction "2_2") (pintype "passive"))
      (node (ref "C41") (pin "2") (pinfunction "2_2") (pintype "passive"))
      (node (ref "C43") (pin "2") (pinfunction "2_2") (pintype "passive"))
      (node (ref "C44") (pin "2") (pinfunction "2_2") (pintype "passive"))
      (node (ref "C45") (pin "2") (pinfunction "2_2") (pintype "passive"))
      (node (ref "C46") (pin "2") (pinfunction "2_2") (pintype "passive"))
      (node (ref "C47") (pin "2") (pinfunction "2_2") (pintype "passive"))
      (node (ref "C48") (pin "2") (pinfunction "2_2") (pintype "passive"))
      (node (ref "C49") (pin "2") (pinfunction "2_2") (pintype "passive"))
      (node (ref "C5") (pin "2") (pinfunction "2_2") (pintype "passive"))
      (node (ref "C50") (pin "2") (pinfunction "2_2") (pintype "passive"))
      (node (ref "C51") (pin "2") (pinfunction "2_2") (pintype "passive"))
      (node (ref "C52") (pin "2") (pinfunction "2_2") (pintype "passive"))
      (node (ref "C53") (pin "2") (pinfunction "2_2") (pintype "passive"))
      (node (ref "C54") (pin "2") (pinfunction "2_2") (pintype "passive"))
      (node (ref "C55") (pin "2") (pinfunction "2_2") (pintype "passive"))
      (node (ref "C56") (pin "2") (pinfunction "2_2") (pintype "passive"))
      (node (ref "C57") (pin "2") (pinfunction "2_2") (pintype "passive"))
      (node (ref "C6") (pin "2") (pinfunction "2_2") (pintype "passive"))
      (node (ref "C7") (pin "2") (pinfunction "2_2") (pintype "passive"))
      (node (ref "C8") (pin "2") (pinfunction "2_2") (pintype "passive"))
      (node (ref "C9") (pin "2") (pinfunction "2_2") (pintype "passive"))
      (node (ref "IC1") (pin "1") (pinfunction "GND_1") (pintype "input"))
      (node (ref "ITG1") (pin "1") (pinfunction "CLKIN_1") (pintype "input"))
      (node (ref "ITG1") (pin "11") (pinfunction "FSYNC_11") (pintype "bidirectional"))
      (node (ref "ITG1") (pin "18") (pinfunction "GND_18") (pintype "bidirectional"))
      (node (ref "ITG1") (pin "9") (pinfunction "AD0_9") (pintype "bidirectional"))
      (node (ref "ITG2") (pin "1") (pinfunction "CLKIN_1") (pintype "input"))
      (node (ref "ITG2") (pin "11") (pinfunction "FSYNC_11") (pintype "bidirectional"))
      (node (ref "ITG2") (pin "18") (pinfunction "GND_18") (pintype "bidirectional"))
      (node (ref "ITG2") (pin "9") (pinfunction "AD0_9") (pintype "bidirectional"))
      (node (ref "ITG3") (pin "1") (pinfunction "CLKIN_1") (pintype "input"))
      (node (ref "ITG3") (pin "11") (pinfunction "FSYNC_11") (pintype "bidirectional"))
      (node (ref "ITG3") (pin "18") (pinfunction "GND_18") (pintype "bidirectional"))
      (node (ref "ITG4") (pin "1") (pinfunction "CLKIN_1") (pintype "input"))
      (node (ref "ITG4") (pin "11") (pinfunction "FSYNC_11") (pintype "bidirectional"))
      (node (ref "ITG4") (pin "18") (pinfunction "GND_18") (pintype "bidirectional"))
      (node (ref "L3G_1") (pin "10") (pinfunction "RSVDG_10") (pintype "bidirectional"))
      (node (ref "L3G_1") (pin "11") (pinfunction "RSDVG_11") (pintype "bidirectional"))
      (node (ref "L3G_1") (pin "12") (pinfunction "RSVDG_12") (pintype "bidirectional"))
      (node (ref "L3G_1") (pin "13") (pinfunction "GND_13") (pintype "bidirectional"))
      (node (ref "L3G_1") (pin "4") (pinfunction "SDO_4") (pintype "bidirectional"))
      (node (ref "L3G_1") (pin "8") (pinfunction "RSVDG_8") (pintype "bidirectional"))
      (node (ref "L3G_1") (pin "9") (pinfunction "RSVDG_9") (pintype "bidirectional"))
      (node (ref "L3G_2") (pin "10") (pinfunction "RSVDG_10") (pintype "bidirectional"))
      (node (ref "L3G_2") (pin "11") (pinfunction "RSDVG_11") (pintype "bidirectional"))
      (node (ref "L3G_2") (pin "12") (pinfunction "RSVDG_12") (pintype "bidirectional"))
      (node (ref "L3G_2") (pin "13") (pinfunction "GND_13") (pintype "bidirectional"))
      (node (ref "L3G_2") (pin "4") (pinfunction "SDO_4") (pintype "bidirectional"))
      (node (ref "L3G_2") (pin "8") (pinfunction "RSVDG_8") (pintype "bidirectional"))
      (node (ref "L3G_2") (pin "9") (pinfunction "RSVDG_9") (pintype "bidirectional"))
      (node (ref "L3G_3") (pin "10") (pinfunction "RSVDG_10") (pintype "bidirectional"))
      (node (ref "L3G_3") (pin "11") (pinfunction "RSDVG_11") (pintype "bidirectional"))
      (node (ref "L3G_3") (pin "12") (pinfunction "RSVDG_12") (pintype "bidirectional"))
      (node (ref "L3G_3") (pin "13") (pinfunction "GND_13") (pintype "bidirectional"))
      (node (ref "L3G_3") (pin "8") (pinfunction "RSVDG_8") (pintype "bidirectional"))
      (node (ref "L3G_3") (pin "9") (pinfunction "RSVDG_9") (pintype "bidirectional"))
      (node (ref "L3G_4") (pin "10") (pinfunction "RSVDG_10") (pintype "bidirectional"))
      (node (ref "L3G_4") (pin "11") (pinfunction "RSDVG_11") (pintype "bidirectional"))
      (node (ref "L3G_4") (pin "12") (pinfunction "RSVDG_12") (pintype "bidirectional"))
      (node (ref "L3G_4") (pin "13") (pinfunction "GND_13") (pintype "bidirectional"))
      (node (ref "L3G_4") (pin "8") (pinfunction "RSVDG_8") (pintype "bidirectional"))
      (node (ref "L3G_4") (pin "9") (pinfunction "RSVDG_9") (pintype "bidirectional"))
      (node (ref "MAG1") (pin "10") (pinfunction "GND_10") (pintype "bidirectional"))
      (node (ref "MAG1") (pin "5") (pinfunction "GND_5") (pintype "bidirectional"))
      (node (ref "MAG2") (pin "10") (pinfunction "GND_10") (pintype "bidirectional"))
      (node (ref "MAG2") (pin "5") (pinfunction "GND_5") (pintype "bidirectional"))
      (node (ref "MPU1") (pin "1") (pinfunction "CLKIN_1") (pintype "input"))
      (node (ref "MPU1") (pin "11") (pinfunction "FSYNC_11") (pintype "bidirectional"))
      (node (ref "MPU1") (pin "18") (pinfunction "GND_18") (pintype "bidirectional"))
      (node (ref "MPU2") (pin "1") (pinfunction "CLKIN_1") (pintype "input"))
      (node (ref "MPU2") (pin "11") (pinfunction "FSYNC_11") (pintype "bidirectional"))
      (node (ref "MPU2") (pin "18") (pinfunction "GND_18") (pintype "bidirectional"))
      (node (ref "MUX1") (pin "1") (pinfunction "A0_1") (pintype "bidirectional"))
      (node (ref "MUX1") (pin "2") (pinfunction "A1_2") (pintype "bidirectional"))
      (node (ref "MUX1") (pin "8") (pinfunction "GND_8") (pintype "bidirectional"))
      (node (ref "MUX2") (pin "1") (pinfunction "A0_1") (pintype "bidirectional"))
      (node (ref "MUX2") (pin "2") (pinfunction "A1_2") (pintype "bidirectional"))
      (node (ref "MUX2") (pin "8") (pinfunction "GND_8") (pintype "bidirectional"))
      (node (ref "P1") (pin "P1_14") (pinfunction "GND_P1_14") (pintype "bidirectional"))
      (node (ref "R11") (pin "1") (pinfunction "1_1") (pintype "passive"))
      (node (ref "R22") (pin "1") (pinfunction "1_1") (pintype "passive"))
      (node (ref "R26") (pin "1") (pinfunction "1_1") (pintype "passive"))
      (node (ref "R38") (pin "1") (pinfunction "1_1") (pintype "passive"))
    )
    (net (code "43") (name "Net-(ACL_1-BYP)") (class "Default")
      (node (ref "ACL_1") (pin "2") (pinfunction "BYP_2") (pintype "bidirectional"))
      (node (ref "C26") (pin "1") (pinfunction "1_1") (pintype "passive"))
    )
    (net (code "44") (name "Net-(ACL_2-BYP)") (class "Default")
      (node (ref "ACL_2") (pin "2") (pinfunction "BYP_2") (pintype "bidirectional"))
      (node (ref "C53") (pin "1") (pinfunction "1_1") (pintype "passive"))
    )
    (net (code "45") (name "Net-(ACL_3-BYP)") (class "Default")
      (node (ref "ACL_3") (pin "2") (pinfunction "BYP_2") (pintype "bidirectional"))
      (node (ref "C27") (pin "1") (pinfunction "1_1") (pintype "passive"))
    )
    (net (code "46") (name "Net-(ACL_4-BYP)") (class "Default")
      (node (ref "ACL_4") (pin "2") (pinfunction "BYP_2") (pintype "bidirectional"))
      (node (ref "C54") (pin "1") (pinfunction "1_1") (pintype "passive"))
    )
    (net (code "47") (name "Net-(ACL_5-BYP)") (class "Default")
      (node (ref "ACL_5") (pin "2") (pinfunction "BYP_2") (pintype "bidirectional"))
      (node (ref "C28") (pin "1") (pinfunction "1_1") (pintype "passive"))
    )
    (net (code "48") (name "Net-(ACL_6-BYP)") (class "Default")
      (node (ref "ACL_6") (pin "2") (pinfunction "BYP_2") (pintype "bidirectional"))
      (node (ref "C55") (pin "1") (pinfunction "1_1") (pintype "passive"))
    )
    (net (code "49") (name "Net-(C15-Pad2)") (class "Default")
      (node (ref "C15") (pin "2") (pinfunction "2_2") (pintype "passive"))
      (node (ref "R11") (pin "2") (pinfunction "2_2") (pintype "passive"))
    )
    (net (code "50") (name "Net-(C31-Pad2)") (class "Default")
      (node (ref "C31") (pin "2") (pinfunction "2_2") (pintype "passive"))
      (node (ref "R22") (pin "2") (pinfunction "2_2") (pintype "passive"))
    )
    (net (code "51") (name "Net-(C42-Pad2)") (class "Default")
      (node (ref "C42") (pin "2") (pinfunction "2_2") (pintype "passive"))
      (node (ref "R26") (pin "2") (pinfunction "2_2") (pintype "passive"))
    )
    (net (code "52") (name "Net-(C58-Pad2)") (class "Default")
      (node (ref "C58") (pin "2") (pinfunction "2_2") (pintype "passive"))
      (node (ref "R38") (pin "2") (pinfunction "2_2") (pintype "passive"))
    )
    (net (code "53") (name "Net-(IC1-IN)") (class "Default")
      (node (ref "IC1") (pin "3") (pinfunction "IN_3") (pintype "input"))
      (node (ref "P1") (pin "P1_2") (pinfunction "5V_P1_2") (pintype "bidirectional"))
    )
    (net (code "54") (name "Net-(ITG1-CPOUT)") (class "Default")
      (node (ref "C17") (pin "1") (pinfunction "1_1") (pintype "passive"))
      (node (ref "ITG1") (pin "20") (pinfunction "CPOUT_20") (pintype "bidirectional"))
    )
    (net (code "55") (name "Net-(ITG1-REGOUT)") (class "Default")
      (node (ref "C10") (pin "1") (pinfunction "1_1") (pintype "passive"))
      (node (ref "ITG1") (pin "10") (pinfunction "REGOUT_10") (pintype "bidirectional"))
    )
    (net (code "56") (name "Net-(ITG2-CPOUT)") (class "Default")
      (node (ref "C44") (pin "1") (pinfunction "1_1") (pintype "passive"))
      (node (ref "ITG2") (pin "20") (pinfunction "CPOUT_20") (pintype "bidirectional"))
    )
    (net (code "57") (name "Net-(ITG2-REGOUT)") (class "Default")
      (node (ref "C37") (pin "1") (pinfunction "1_1") (pintype "passive"))
      (node (ref "ITG2") (pin "10") (pinfunction "REGOUT_10") (pintype "bidirectional"))
    )
    (net (code "58") (name "Net-(ITG3-CPOUT)") (class "Default")
      (node (ref "C18") (pin "1") (pinfunction "1_1") (pintype "passive"))
      (node (ref "ITG3") (pin "20") (pinfunction "CPOUT_20") (pintype "bidirectional"))
    )
    (net (code "59") (name "Net-(ITG3-REGOUT)") (class "Default")
      (node (ref "C11") (pin "1") (pinfunction "1_1") (pintype "passive"))
      (node (ref "ITG3") (pin "10") (pinfunction "REGOUT_10") (pintype "bidirectional"))
    )
    (net (code "60") (name "Net-(ITG4-CPOUT)") (class "Default")
      (node (ref "C45") (pin "1") (pinfunction "1_1") (pintype "passive"))
      (node (ref "ITG4") (pin "20") (pinfunction "CPOUT_20") (pintype "bidirectional"))
    )
    (net (code "61") (name "Net-(ITG4-REGOUT)") (class "Default")
      (node (ref "C38") (pin "1") (pinfunction "1_1") (pintype "passive"))
      (node (ref "ITG4") (pin "10") (pinfunction "REGOUT_10") (pintype "bidirectional"))
    )
    (net (code "62") (name "Net-(L3G_1-PLL)") (class "Default")
      (node (ref "C12") (pin "1") (pinfunction "1_1") (pintype "passive"))
      (node (ref "C15") (pin "1") (pinfunction "1_1") (pintype "passive"))
      (node (ref "L3G_1") (pin "14") (pinfunction "PLL_14") (pintype "bidirectional"))
    )
    (net (code "63") (name "Net-(L3G_2-PLL)") (class "Default")
      (node (ref "C39") (pin "1") (pinfunction "1_1") (pintype "passive"))
      (node (ref "C42") (pin "1") (pinfunction "1_1") (pintype "passive"))
      (node (ref "L3G_2") (pin "14") (pinfunction "PLL_14") (pintype "bidirectional"))
    )
    (net (code "64") (name "Net-(L3G_3-PLL)") (class "Default")
      (node (ref "C30") (pin "1") (pinfunction "1_1") (pintype "passive"))
      (node (ref "C31") (pin "1") (pinfunction "1_1") (pintype "passive"))
      (node (ref "L3G_3") (pin "14") (pinfunction "PLL_14") (pintype "bidirectional"))
    )
    (net (code "65") (name "Net-(L3G_4-PLL)") (class "Default")
      (node (ref "C57") (pin "1") (pinfunction "1_1") (pintype "passive"))
      (node (ref "C58") (pin "1") (pinfunction "1_1") (pintype "passive"))
      (node (ref "L3G_4") (pin "14") (pinfunction "PLL_14") (pintype "bidirectional"))
    )
    (net (code "66") (name "Net-(MAG1-CAP-A)") (class "Default")
      (node (ref "C1") (pin "1") (pinfunction "1_1") (pintype "passive"))
      (node (ref "MAG1") (pin "1") (pinfunction "CAP-A_1") (pintype "bidirectional"))
    )
    (net (code "67") (name "Net-(MAG1-CAP-R)") (class "Default")
      (node (ref "C3") (pin "1") (pinfunction "1_1") (pintype "passive"))
      (node (ref "MAG1") (pin "4") (pinfunction "CAP-R_4") (pintype "bidirectional"))
    )
    (net (code "68") (name "Net-(MAG2-CAP-A)") (class "Default")
      (node (ref "C2") (pin "1") (pinfunction "1_1") (pintype "passive"))
      (node (ref "MAG2") (pin "1") (pinfunction "CAP-A_1") (pintype "bidirectional"))
    )
    (net (code "69") (name "Net-(MAG2-CAP-R)") (class "Default")
      (node (ref "C4") (pin "1") (pinfunction "1_1") (pintype "passive"))
      (node (ref "MAG2") (pin "4") (pinfunction "CAP-R_4") (pintype "bidirectional"))
    )
    (net (code "70") (name "Net-(MPU1-CPOUT)") (class "Default")
      (node (ref "C16") (pin "1") (pinfunction "1_1") (pintype "passive"))
      (node (ref "MPU1") (pin "20") (pinfunction "CPOUT_20") (pintype "bidirectional"))
    )
    (net (code "71") (name "Net-(MPU1-REGOUT)") (class "Default")
      (node (ref "C6") (pin "1") (pinfunction "1_1") (pintype "passive"))
      (node (ref "MPU1") (pin "10") (pinfunction "REGOUT_10") (pintype "bidirectional"))
    )
    (net (code "72") (name "Net-(MPU2-CPOUT)") (class "Default")
      (node (ref "C43") (pin "1") (pinfunction "1_1") (pintype "passive"))
      (node (ref "MPU2") (pin "20") (pinfunction "CPOUT_20") (pintype "bidirectional"))
    )
    (net (code "73") (name "Net-(MPU2-REGOUT)") (class "Default")
      (node (ref "C33") (pin "1") (pinfunction "1_1") (pintype "passive"))
      (node (ref "MPU2") (pin "10") (pinfunction "REGOUT_10") (pintype "bidirectional"))
    )
    (net (code "74") (name "Net-(MUX1-RESET)") (class "Default")
      (node (ref "MUX1") (pin "3") (pinfunction "RESET_3") (pintype "bidirectional"))
      (node (ref "R1") (pin "2") (pinfunction "2_2") (pintype "passive"))
    )
    (net (code "75") (name "Net-(MUX2-RESET)") (class "Default")
      (node (ref "MUX2") (pin "3") (pinfunction "RESET_3") (pintype "bidirectional"))
      (node (ref "R2") (pin "2") (pinfunction "2_2") (pintype "passive"))
    )
    (net (code "76") (name "unconnected-(ACL_1-INT1-Pad11)") (class "Default")
      (node (ref "ACL_1") (pin "11") (pinfunction "INT1_11") (pintype "bidirectional"))
    )
    (net (code "77") (name "unconnected-(ACL_1-INT2-Pad9)") (class "Default")
      (node (ref "ACL_1") (pin "9") (pinfunction "INT2_9") (pintype "bidirectional"))
    )
    (net (code "78") (name "unconnected-(ACL_2-INT1-Pad11)") (class "Default")
      (node (ref "ACL_2") (pin "11") (pinfunction "INT1_11") (pintype "bidirectional"))
    )
    (net (code "79") (name "unconnected-(ACL_2-INT2-Pad9)") (class "Default")
      (node (ref "ACL_2") (pin "9") (pinfunction "INT2_9") (pintype "bidirectional"))
    )
    (net (code "80") (name "unconnected-(ACL_3-INT1-Pad11)") (class "Default")
      (node (ref "ACL_3") (pin "11") (pinfunction "INT1_11") (pintype "bidirectional"))
    )
    (net (code "81") (name "unconnected-(ACL_3-INT2-Pad9)") (class "Default")
      (node (ref "ACL_3") (pin "9") (pinfunction "INT2_9") (pintype "bidirectional"))
    )
    (net (code "82") (name "unconnected-(ACL_4-INT1-Pad11)") (class "Default")
      (node (ref "ACL_4") (pin "11") (pinfunction "INT1_11") (pintype "bidirectional"))
    )
    (net (code "83") (name "unconnected-(ACL_4-INT2-Pad9)") (class "Default")
      (node (ref "ACL_4") (pin "9") (pinfunction "INT2_9") (pintype "bidirectional"))
    )
    (net (code "84") (name "unconnected-(ACL_5-INT1-Pad11)") (class "Default")
      (node (ref "ACL_5") (pin "11") (pinfunction "INT1_11") (pintype "bidirectional"))
    )
    (net (code "85") (name "unconnected-(ACL_5-INT2-Pad9)") (class "Default")
      (node (ref "ACL_5") (pin "9") (pinfunction "INT2_9") (pintype "bidirectional"))
    )
    (net (code "86") (name "unconnected-(ACL_6-INT1-Pad11)") (class "Default")
      (node (ref "ACL_6") (pin "11") (pinfunction "INT1_11") (pintype "bidirectional"))
    )
    (net (code "87") (name "unconnected-(ACL_6-INT2-Pad9)") (class "Default")
      (node (ref "ACL_6") (pin "9") (pinfunction "INT2_9") (pintype "bidirectional"))
    )
    (net (code "88") (name "unconnected-(ITG1-CLKOUT-Pad22)") (class "Default")
      (node (ref "ITG1") (pin "22") (pinfunction "CLKOUT_22") (pintype "bidirectional"))
    )
    (net (code "89") (name "unconnected-(ITG1-INT-Pad12)") (class "Default")
      (node (ref "ITG1") (pin "12") (pinfunction "INT_12") (pintype "bidirectional"))
    )
    (net (code "90") (name "unconnected-(ITG2-CLKOUT-Pad22)") (class "Default")
      (node (ref "ITG2") (pin "22") (pinfunction "CLKOUT_22") (pintype "bidirectional"))
    )
    (net (code "91") (name "unconnected-(ITG2-INT-Pad12)") (class "Default")
      (node (ref "ITG2") (pin "12") (pinfunction "INT_12") (pintype "bidirectional"))
    )
    (net (code "92") (name "unconnected-(ITG3-CLKOUT-Pad22)") (class "Default")
      (node (ref "ITG3") (pin "22") (pinfunction "CLKOUT_22") (pintype "bidirectional"))
    )
    (net (code "93") (name "unconnected-(ITG3-INT-Pad12)") (class "Default")
      (node (ref "ITG3") (pin "12") (pinfunction "INT_12") (pintype "bidirectional"))
    )
    (net (code "94") (name "unconnected-(ITG4-CLKOUT-Pad22)") (class "Default")
      (node (ref "ITG4") (pin "22") (pinfunction "CLKOUT_22") (pintype "bidirectional"))
    )
    (net (code "95") (name "unconnected-(ITG4-INT-Pad12)") (class "Default")
      (node (ref "ITG4") (pin "12") (pinfunction "INT_12") (pintype "bidirectional"))
    )
    (net (code "96") (name "unconnected-(L3G_1-INT1-Pad7)") (class "Default")
      (node (ref "L3G_1") (pin "7") (pinfunction "INT1_7") (pintype "bidirectional"))
    )
    (net (code "97") (name "unconnected-(L3G_1-INT2-Pad6)") (class "Default")
      (node (ref "L3G_1") (pin "6") (pinfunction "INT2_6") (pintype "bidirectional"))
    )
    (net (code "98") (name "unconnected-(L3G_2-INT1-Pad7)") (class "Default")
      (node (ref "L3G_2") (pin "7") (pinfunction "INT1_7") (pintype "bidirectional"))
    )
    (net (code "99") (name "unconnected-(L3G_2-INT2-Pad6)") (class "Default")
      (node (ref "L3G_2") (pin "6") (pinfunction "INT2_6") (pintype "bidirectional"))
    )
    (net (code "100") (name "unconnected-(L3G_3-INT1-Pad7)") (class "Default")
      (node (ref "L3G_3") (pin "7") (pinfunction "INT1_7") (pintype "bidirectional"))
    )
    (net (code "101") (name "unconnected-(L3G_3-INT2-Pad6)") (class "Default")
      (node (ref "L3G_3") (pin "6") (pinfunction "INT2_6") (pintype "bidirectional"))
    )
    (net (code "102") (name "unconnected-(L3G_4-INT1-Pad7)") (class "Default")
      (node (ref "L3G_4") (pin "7") (pinfunction "INT1_7") (pintype "bidirectional"))
    )
    (net (code "103") (name "unconnected-(L3G_4-INT2-Pad6)") (class "Default")
      (node (ref "L3G_4") (pin "6") (pinfunction "INT2_6") (pintype "bidirectional"))
    )
    (net (code "104") (name "unconnected-(MAG1-INT1-Pad9)") (class "Default")
      (node (ref "MAG1") (pin "9") (pinfunction "INT1_9") (pintype "bidirectional"))
    )
    (net (code "105") (name "unconnected-(MAG2-INT1-Pad9)") (class "Default")
      (node (ref "MAG2") (pin "9") (pinfunction "INT1_9") (pintype "bidirectional"))
    )
    (net (code "106") (name "unconnected-(MPU1-CLKOUT-Pad22)") (class "Default")
      (node (ref "MPU1") (pin "22") (pinfunction "CLKOUT_22") (pintype "bidirectional"))
    )
    (net (code "107") (name "unconnected-(MPU1-INT-Pad12)") (class "Default")
      (node (ref "MPU1") (pin "12") (pinfunction "INT_12") (pintype "bidirectional"))
    )
    (net (code "108") (name "unconnected-(MPU2-CLKOUT-Pad22)") (class "Default")
      (node (ref "MPU2") (pin "22") (pinfunction "CLKOUT_22") (pintype "bidirectional"))
    )
    (net (code "109") (name "unconnected-(MPU2-INT-Pad12)") (class "Default")
      (node (ref "MPU2") (pin "12") (pinfunction "INT_12") (pintype "bidirectional"))
    )
    (net (code "110") (name "unconnected-(MUX1-SC3-Pad12)") (class "Default")
      (node (ref "MUX1") (pin "12") (pinfunction "SC3_12") (pintype "bidirectional"))
    )
    (net (code "111") (name "unconnected-(MUX1-SD3-Pad11)") (class "Default")
      (node (ref "MUX1") (pin "11") (pinfunction "SD3_11") (pintype "bidirectional"))
    )
    (net (code "112") (name "unconnected-(MUX2-SC3-Pad12)") (class "Default")
      (node (ref "MUX2") (pin "12") (pinfunction "SC3_12") (pintype "bidirectional"))
    )
    (net (code "113") (name "unconnected-(MUX2-SD3-Pad11)") (class "Default")
      (node (ref "MUX2") (pin "11") (pinfunction "SD3_11") (pintype "bidirectional"))
    )
    (net (code "114") (name "unconnected-(P1-3V3-PadP1_1)") (class "Default")
      (node (ref "P1") (pin "P1_1") (pinfunction "3V3_P1_1") (pintype "bidirectional"))
    )
    (net (code "115") (name "unconnected-(P1-3V3-PadP1_17)") (class "Default")
      (node (ref "P1") (pin "P1_17") (pinfunction "3V3_P1_17") (pintype "bidirectional"))
    )
    (net (code "116") (name "unconnected-(P1-5V-PadP1_4)") (class "Default")
      (node (ref "P1") (pin "P1_4") (pinfunction "5V_P1_4") (pintype "bidirectional"))
    )
    (net (code "117") (name "unconnected-(P1-GND-PadP1_6)") (class "Default")
      (node (ref "P1") (pin "P1_6") (pinfunction "GND_P1_6") (pintype "bidirectional"))
    )
    (net (code "118") (name "unconnected-(P1-GND-PadP1_9)") (class "Default")
      (node (ref "P1") (pin "P1_9") (pinfunction "GND_P1_9") (pintype "bidirectional"))
    )
    (net (code "119") (name "unconnected-(P1-GND-PadP1_20)") (class "Default")
      (node (ref "P1") (pin "P1_20") (pinfunction "GND_P1_20") (pintype "bidirectional"))
    )
    (net (code "120") (name "unconnected-(P1-GND-PadP1_25)") (class "Default")
      (node (ref "P1") (pin "P1_25") (pinfunction "GND_P1_25") (pintype "bidirectional"))
    )
    (net (code "121") (name "unconnected-(P1-GPIO4,GPCLK0-PadP1_7)") (class "Default")
      (node (ref "P1") (pin "P1_7") (pinfunction "GPIO4,GPCLK0_P1_7") (pintype "bidirectional"))
    )
    (net (code "122") (name "unconnected-(P1-GPIO7,SPI0_CE1-PadP1_26)") (class "Default")
      (node (ref "P1") (pin "P1_26") (pinfunction "GPIO7,SPI0_CE1_P1_26") (pintype "bidirectional"))
    )
    (net (code "123") (name "unconnected-(P1-GPIO8,SPI0_CE0-PadP1_24)") (class "Default")
      (node (ref "P1") (pin "P1_24") (pinfunction "GPIO8,SPI0_CE0_P1_24") (pintype "bidirectional"))
    )
    (net (code "124") (name "unconnected-(P1-GPIO9_MISO-PadP1_21)") (class "Default")
      (node (ref "P1") (pin "P1_21") (pinfunction "GPIO9_MISO_P1_21") (pintype "bidirectional"))
    )
    (net (code "125") (name "unconnected-(P1-GPIO10_MOSI-PadP1_19)") (class "Default")
      (node (ref "P1") (pin "P1_19") (pinfunction "GPIO10_MOSI_P1_19") (pintype "bidirectional"))
    )
    (net (code "126") (name "unconnected-(P1-GPIO11_SCLK-PadP1_23)") (class "Default")
      (node (ref "P1") (pin "P1_23") (pinfunction "GPIO11_SCLK_P1_23") (pintype "bidirectional"))
    )
    (net (code "127") (name "unconnected-(P1-GPIO14,UART0_TXD-PadP1_8)") (class "Default")
      (node (ref "P1") (pin "P1_8") (pinfunction "GPIO14,UART0_TXD_P1_8") (pintype "bidirectional"))
    )
    (net (code "128") (name "unconnected-(P1-GPIO15,UART0_RXD-PadP1_10)") (class "Default")
      (node (ref "P1") (pin "P1_10") (pinfunction "GPIO15,UART0_RXD_P1_10") (pintype "bidirectional"))
    )
    (net (code "129") (name "unconnected-(P1-GPIO17-PadP1_11)") (class "Default")
      (node (ref "P1") (pin "P1_11") (pinfunction "GPIO17_P1_11") (pintype "bidirectional"))
    )
    (net (code "130") (name "unconnected-(P1-GPIO18-PadP1_12)") (class "Default")
      (node (ref "P1") (pin "P1_12") (pinfunction "GPIO18_P1_12") (pintype "bidirectional"))
    )
    (net (code "131") (name "unconnected-(P1-GPIO22-PadP1_15)") (class "Default")
      (node (ref "P1") (pin "P1_15") (pinfunction "GPIO22_P1_15") (pintype "bidirectional"))
    )
    (net (code "132") (name "unconnected-(P1-GPIO23-PadP1_16)") (class "Default")
      (node (ref "P1") (pin "P1_16") (pinfunction "GPIO23_P1_16") (pintype "bidirectional"))
    )
    (net (code "133") (name "unconnected-(P1-GPIO24-PadP1_18)") (class "Default")
      (node (ref "P1") (pin "P1_18") (pinfunction "GPIO24_P1_18") (pintype "bidirectional"))
    )
    (net (code "134") (name "unconnected-(P1-GPIO25-PadP1_22)") (class "Default")
      (node (ref "P1") (pin "P1_22") (pinfunction "GPIO25_P1_22") (pintype "bidirectional"))
    )
    (net (code "135") (name "unconnected-(P1-GPIO27-PadP1_13)") (class "Default")
      (node (ref "P1") (pin "P1_13") (pinfunction "GPIO27_P1_13") (pintype "bidirectional"))
    )
    (net (code "136") (name "unconnected-(P5-3V3-PadP5_2)") (class "Default")
      (node (ref "P5") (pin "P5_2") (pinfunction "3V3_P5_2") (pintype "bidirectional"))
    )
    (net (code "137") (name "unconnected-(P5-5V-PadP5_1)") (class "Default")
      (node (ref "P5") (pin "P5_1") (pinfunction "5V_P5_1") (pintype "bidirectional"))
    )
    (net (code "138") (name "unconnected-(P5-GND-PadP5_7)") (class "Default")
      (node (ref "P5") (pin "P5_7") (pinfunction "GND_P5_7") (pintype "bidirectional"))
    )
    (net (code "139") (name "unconnected-(P5-GND-PadP5_8)") (class "Default")
      (node (ref "P5") (pin "P5_8") (pinfunction "GND_P5_8") (pintype "bidirectional"))
    )
    (net (code "140") (name "unconnected-(P5-GPIO28-PadP5_3)") (class "Default")
      (node (ref "P5") (pin "P5_3") (pinfunction "GPIO28_P5_3") (pintype "bidirectional"))
    )
    (net (code "141") (name "unconnected-(P5-GPIO29-PadP5_4)") (class "Default")
      (node (ref "P5") (pin "P5_4") (pinfunction "GPIO29_P5_4") (pintype "bidirectional"))
    )
  )
)
